# harp_behavior.net
KiCad netlist of a schematic drawn in EAGLE
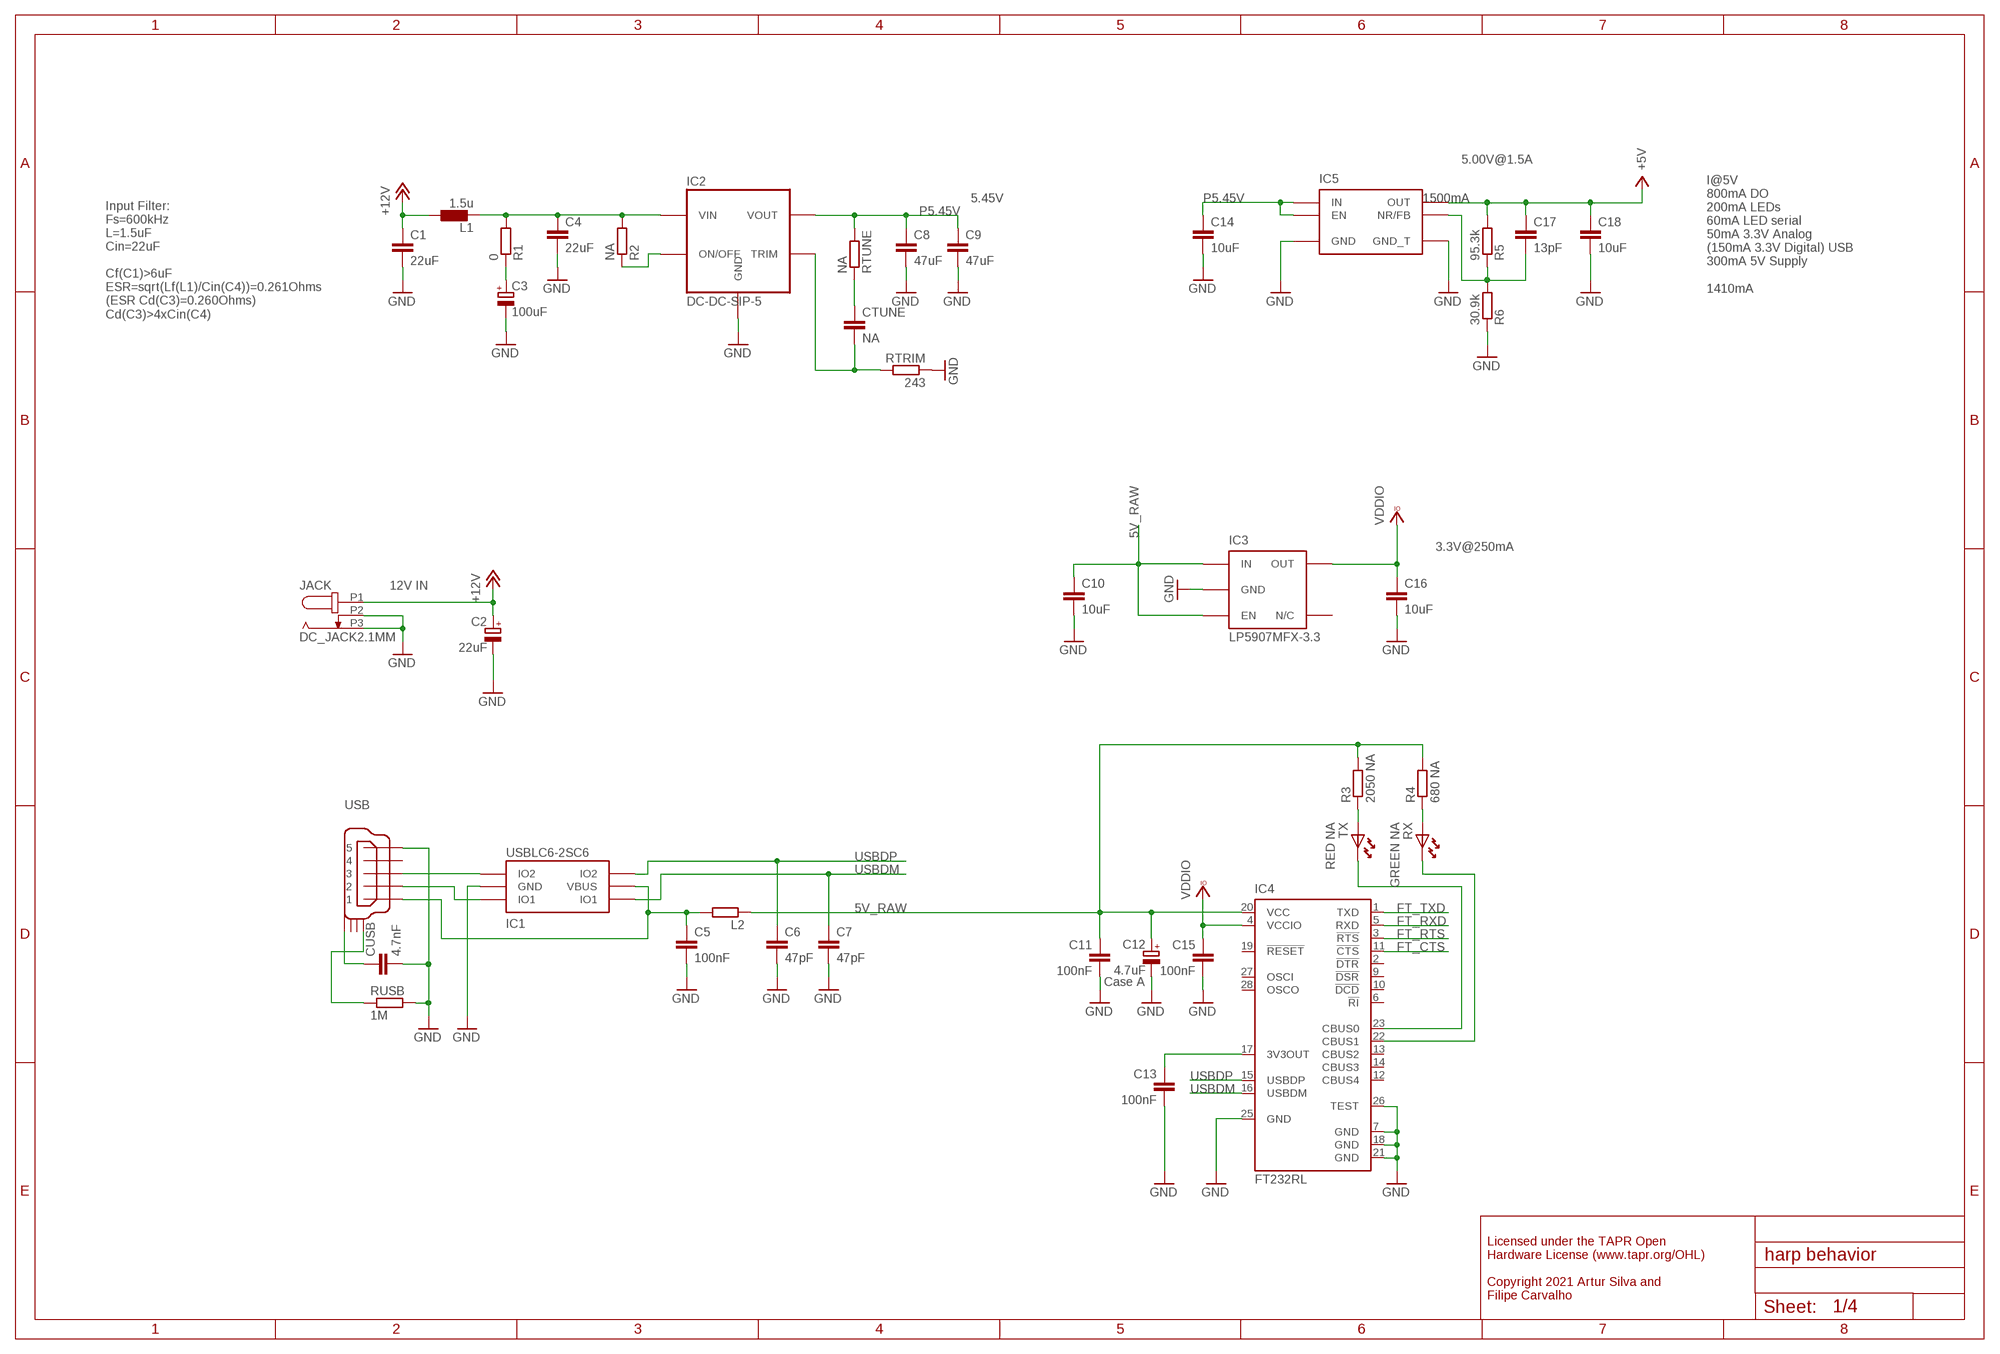
[diagram p0: schematic, sheet 1]
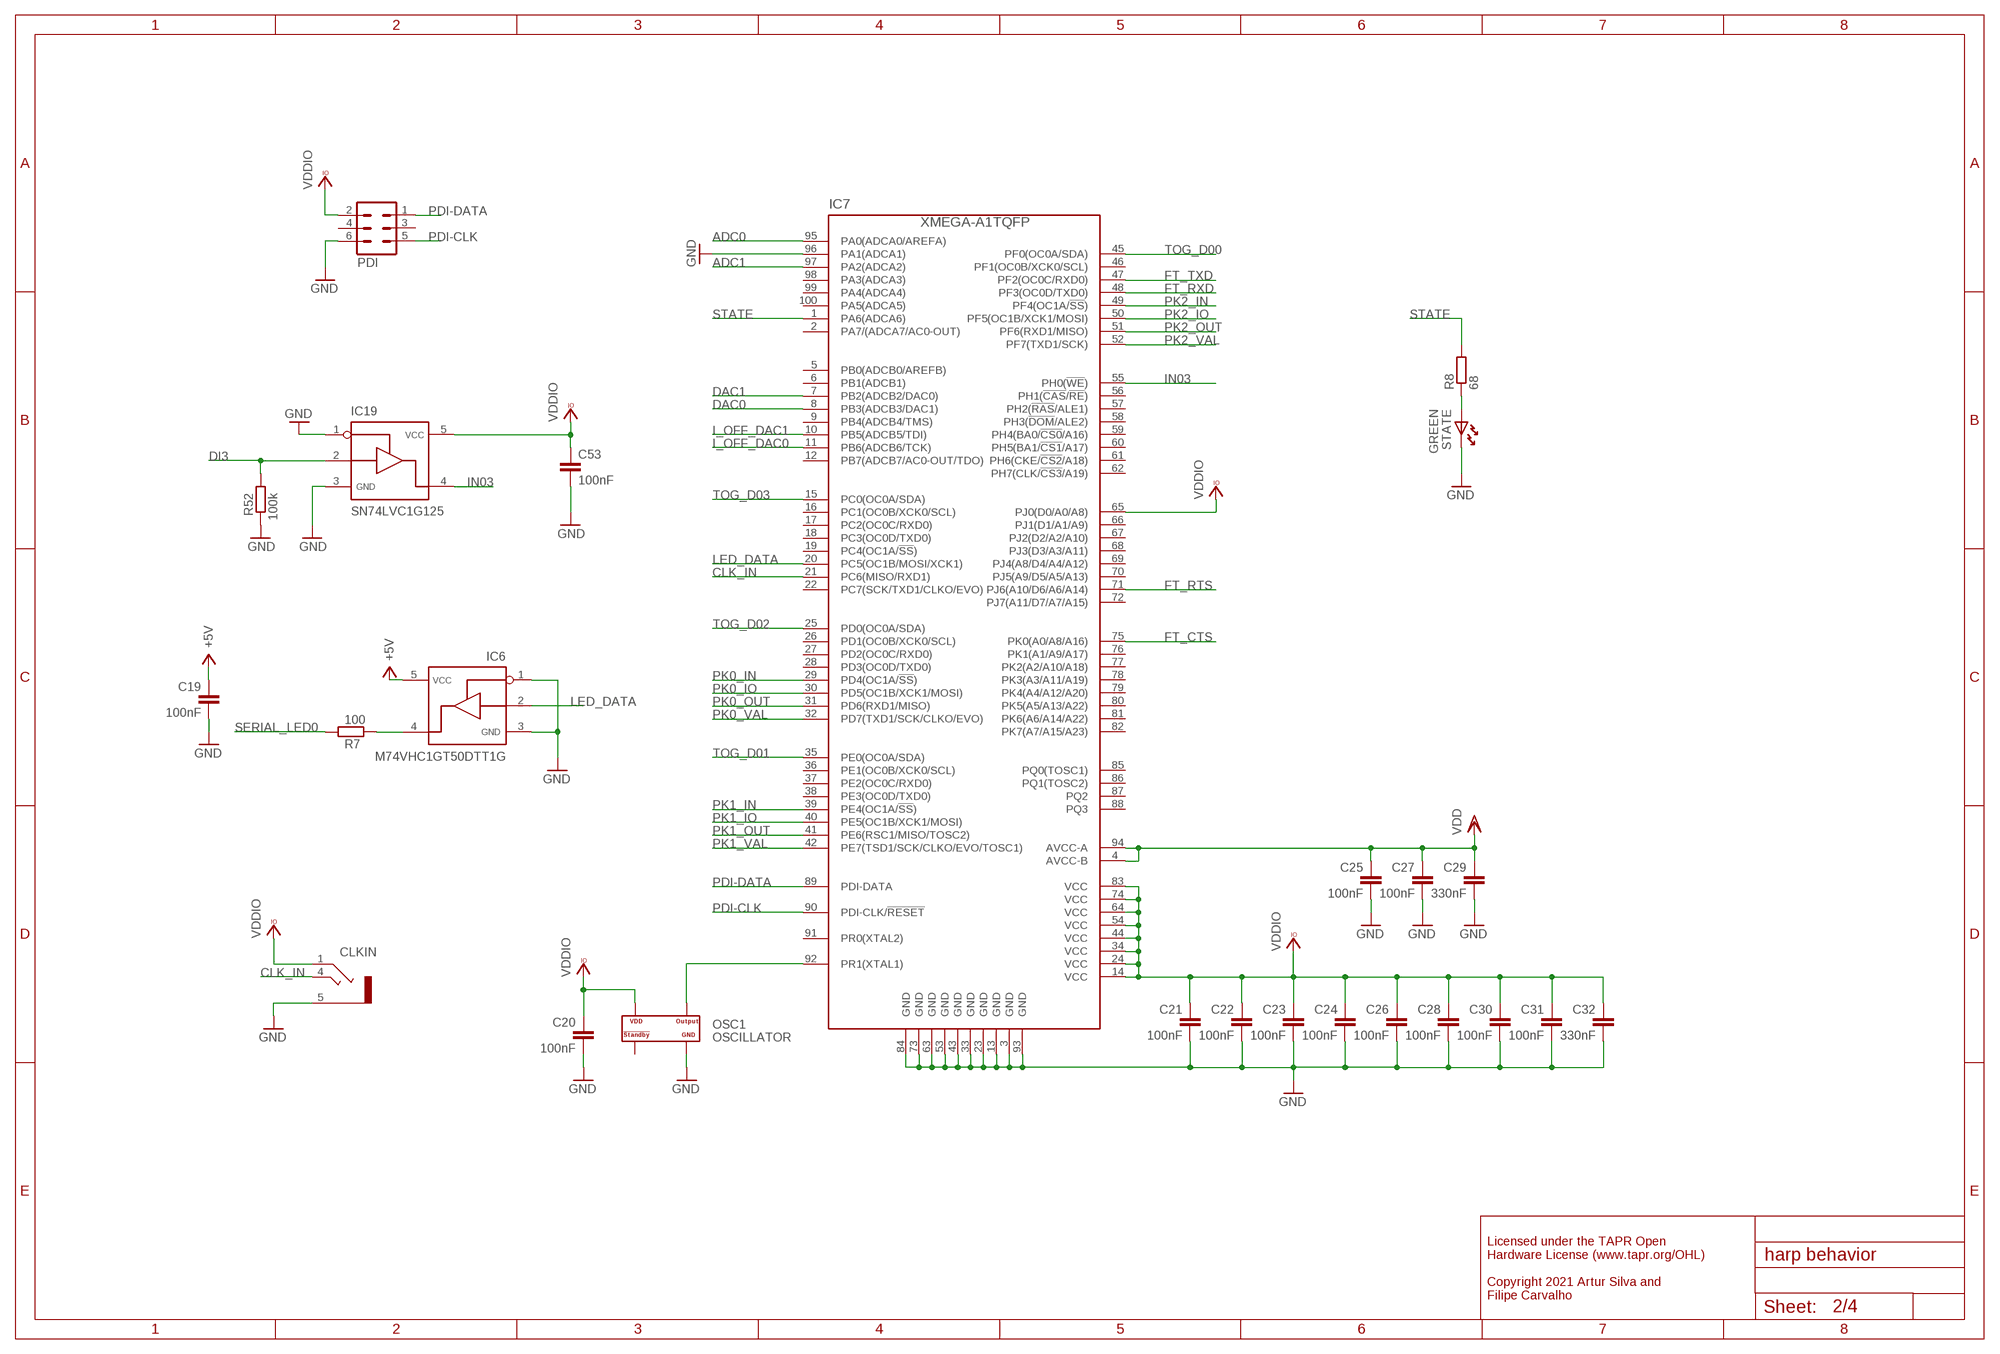
[diagram p1: schematic, sheet 2]
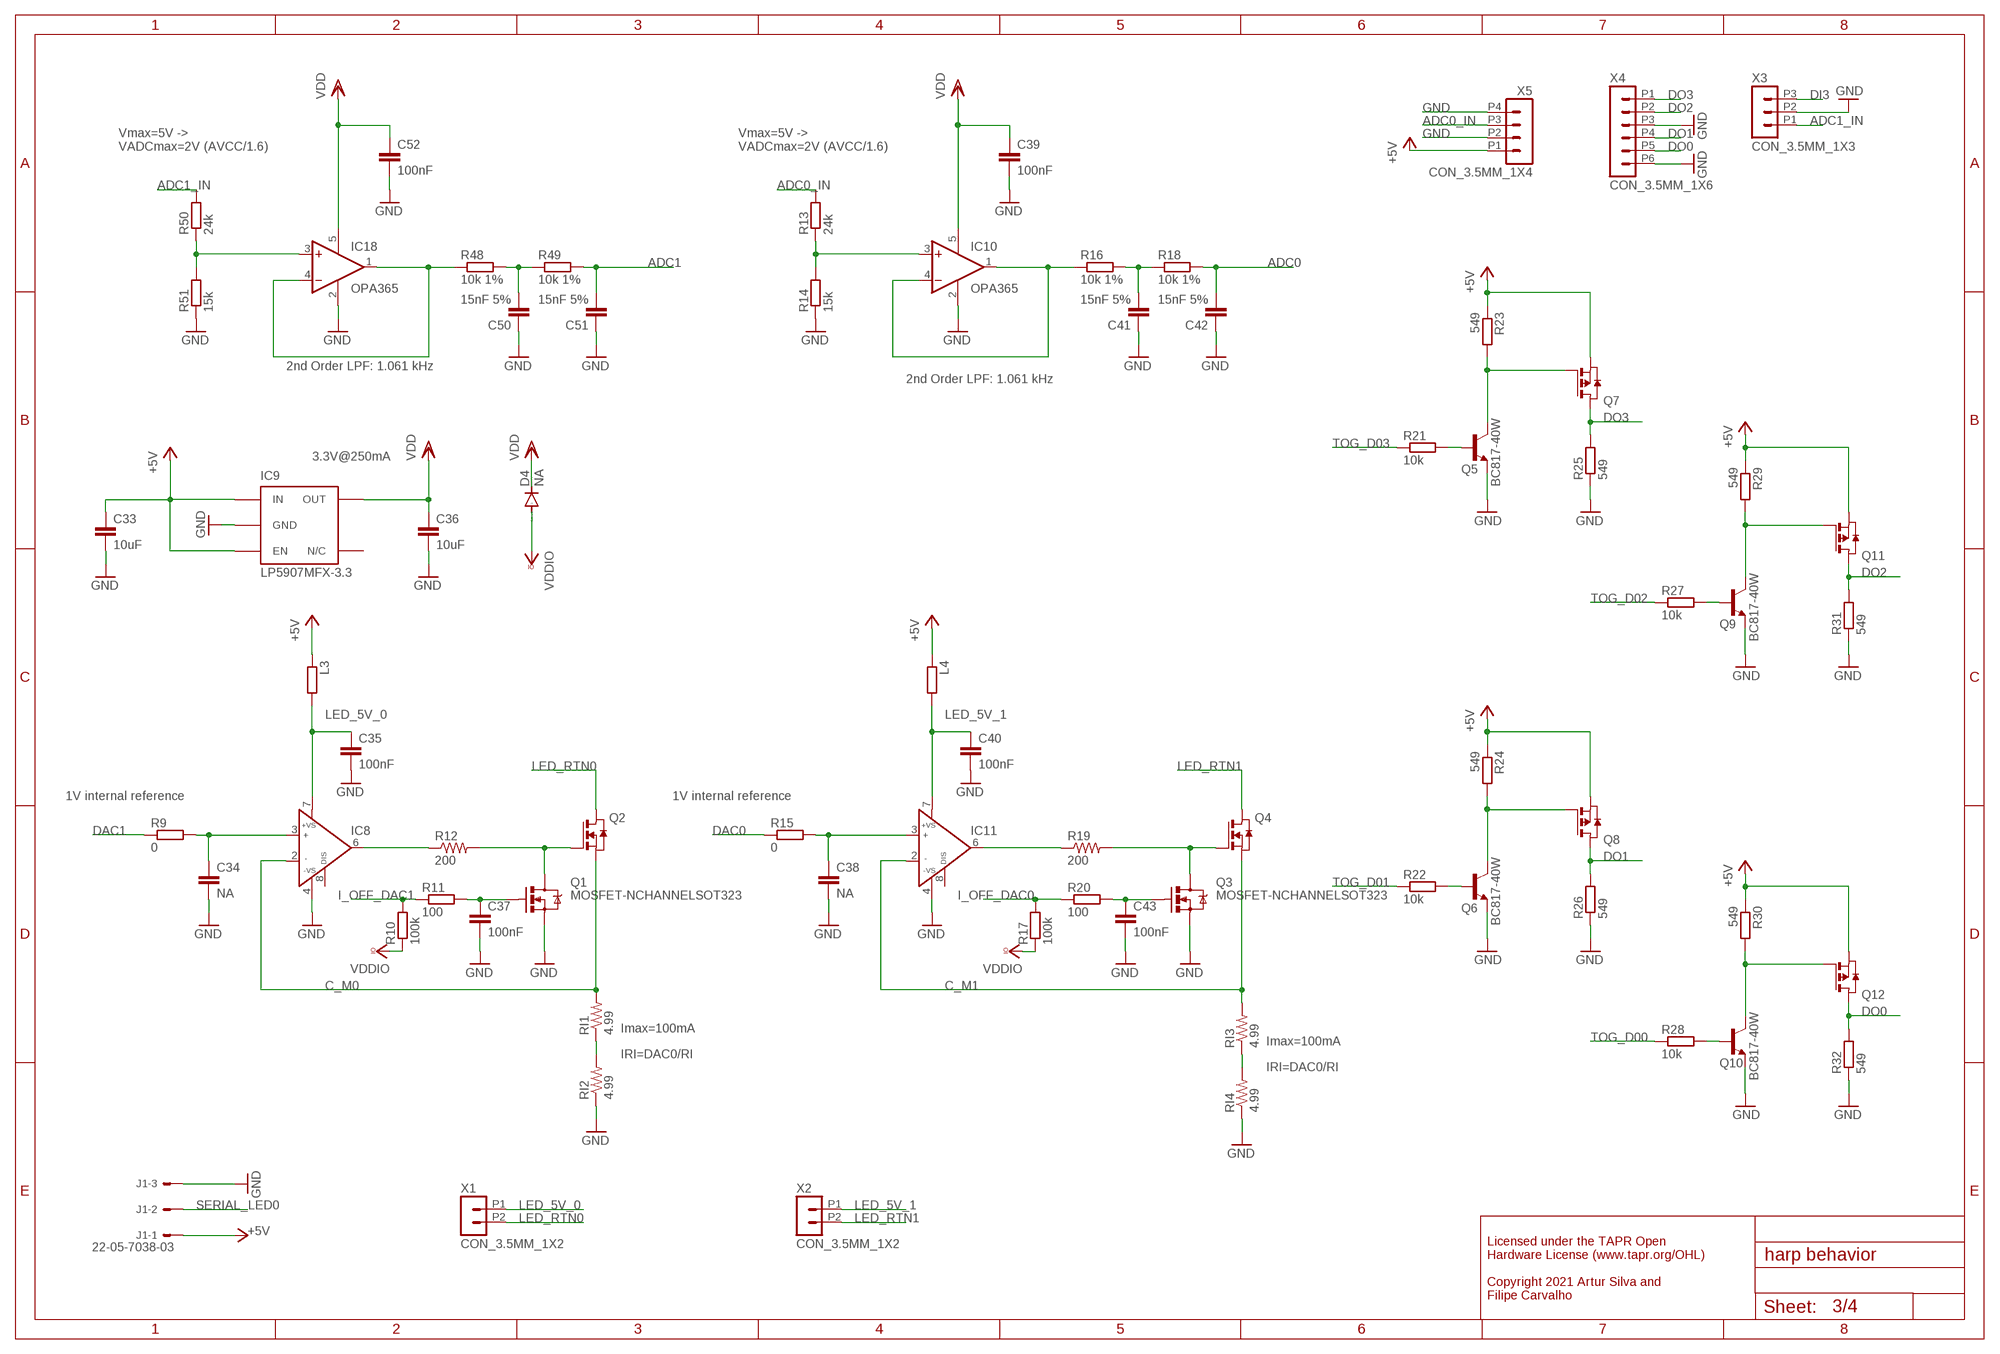
[diagram p2: schematic, sheet 3]
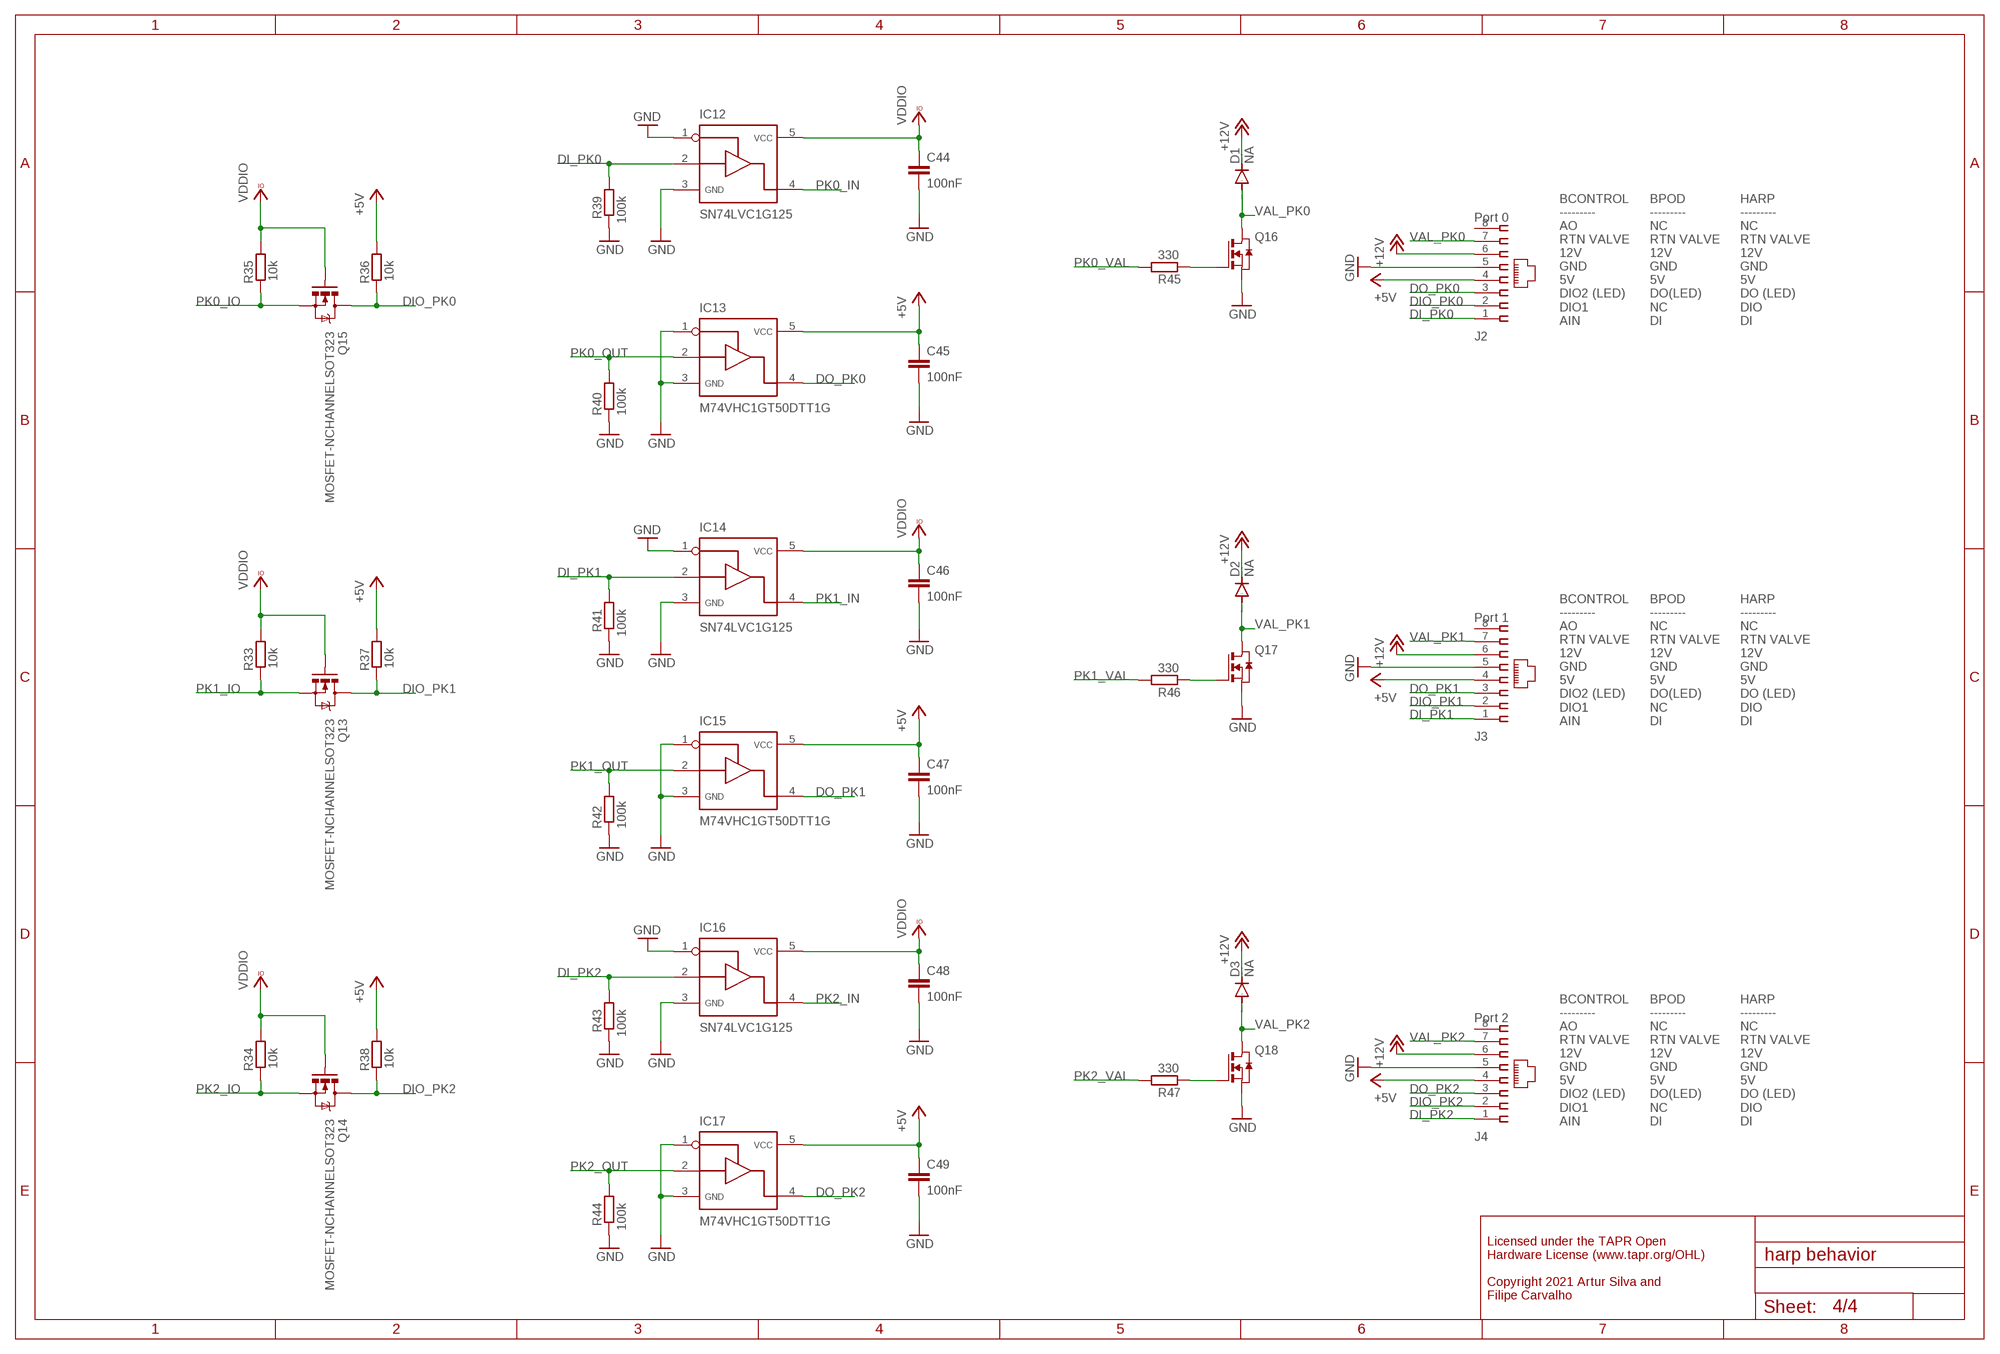
[diagram p3: schematic, sheet 4]

(export (version "E")
  (design (tool "Eeschema 10.0.6"))
  (components
    (comp (ref "C44")
      (value "100nF")
      (footprint "eagle-import:C0402")
      (libsource (lib "eagle-import") (part "C-EUC0402"))
    )
    (comp (ref "C45")
      (value "100nF")
      (footprint "eagle-import:C0402")
      (libsource (lib "eagle-import") (part "C-EUC0402"))
    )
    (comp (ref "C46")
      (value "100nF")
      (footprint "eagle-import:C0402")
      (libsource (lib "eagle-import") (part "C-EUC0402"))
    )
    (comp (ref "C47")
      (value "100nF")
      (footprint "eagle-import:C0402")
      (libsource (lib "eagle-import") (part "C-EUC0402"))
    )
    (comp (ref "C48")
      (value "100nF")
      (footprint "eagle-import:C0402")
      (libsource (lib "eagle-import") (part "C-EUC0402"))
    )
    (comp (ref "C49")
      (value "100nF")
      (footprint "eagle-import:C0402")
      (libsource (lib "eagle-import") (part "C-EUC0402"))
    )
    (comp (ref "D1")
      (value "NA")
      (footprint "eagle-import:SOD-323-DIODE")
      (libsource (lib "eagle-import") (part "DIODE"))
    )
    (comp (ref "D2")
      (value "NA")
      (footprint "eagle-import:SOD-323-DIODE")
      (libsource (lib "eagle-import") (part "DIODE"))
    )
    (comp (ref "D3")
      (value "NA")
      (footprint "eagle-import:SOD-323-DIODE")
      (libsource (lib "eagle-import") (part "DIODE"))
    )
    (comp (ref "IC12")
      (value "SN74LVC1G125")
      (footprint "eagle-import:SOT23-5")
      (libsource (lib "eagle-import") (part "SN74LVC1G125"))
    )
    (comp (ref "IC13")
      (value "M74VHC1GT50DTT1G")
      (footprint "eagle-import:SOT23-5")
      (libsource (lib "eagle-import") (part "SN74LVC1G125"))
    )
    (comp (ref "IC14")
      (value "SN74LVC1G125")
      (footprint "eagle-import:SOT23-5")
      (libsource (lib "eagle-import") (part "SN74LVC1G125"))
    )
    (comp (ref "IC15")
      (value "M74VHC1GT50DTT1G")
      (footprint "eagle-import:SOT23-5")
      (libsource (lib "eagle-import") (part "SN74LVC1G125"))
    )
    (comp (ref "IC16")
      (value "SN74LVC1G125")
      (footprint "eagle-import:SOT23-5")
      (libsource (lib "eagle-import") (part "SN74LVC1G125"))
    )
    (comp (ref "IC17")
      (value "M74VHC1GT50DTT1G")
      (footprint "eagle-import:SOT23-5")
      (libsource (lib "eagle-import") (part "SN74LVC1G125"))
    )
    (comp (ref "J2")
      (value "Port 0")
      (footprint "eagle-import:520426-4")
      (libsource (lib "eagle-import") (part "520426-4"))
    )
    (comp (ref "J3")
      (value "Port 1")
      (footprint "eagle-import:520426-4")
      (libsource (lib "eagle-import") (part "520426-4"))
    )
    (comp (ref "J4")
      (value "Port 2")
      (footprint "eagle-import:520426-4")
      (libsource (lib "eagle-import") (part "520426-4"))
    )
    (comp (ref "Q13")
      (value "MOSFET-NCHANNELSOT323")
      (footprint "eagle-import:SOT323")
      (libsource (lib "eagle-import") (part "MOSFET-NCHANNELSOT323"))
    )
    (comp (ref "Q14")
      (value "MOSFET-NCHANNELSOT323")
      (footprint "eagle-import:SOT323")
      (libsource (lib "eagle-import") (part "MOSFET-NCHANNELSOT323"))
    )
    (comp (ref "Q15")
      (value "MOSFET-NCHANNELSOT323")
      (footprint "eagle-import:SOT323")
      (libsource (lib "eagle-import") (part "MOSFET-NCHANNELSOT323"))
    )
    (comp (ref "Q16")
      (value "NMOSSOT223")
      (footprint "eagle-import:SOT223")
      (libsource (lib "eagle-import") (part "NMOSSOT223"))
    )
    (comp (ref "Q17")
      (value "NMOSSOT223")
      (footprint "eagle-import:SOT223")
      (libsource (lib "eagle-import") (part "NMOSSOT223"))
    )
    (comp (ref "Q18")
      (value "NMOSSOT223")
      (footprint "eagle-import:SOT223")
      (libsource (lib "eagle-import") (part "NMOSSOT223"))
    )
    (comp (ref "R33")
      (value "10k")
      (footprint "eagle-import:R0402")
      (libsource (lib "eagle-import") (part "R-EU_R0402"))
    )
    (comp (ref "R34")
      (value "10k")
      (footprint "eagle-import:R0402")
      (libsource (lib "eagle-import") (part "R-EU_R0402"))
    )
    (comp (ref "R35")
      (value "10k")
      (footprint "eagle-import:R0402")
      (libsource (lib "eagle-import") (part "R-EU_R0402"))
    )
    (comp (ref "R36")
      (value "10k")
      (footprint "eagle-import:R0402")
      (libsource (lib "eagle-import") (part "R-EU_R0402"))
    )
    (comp (ref "R37")
      (value "10k")
      (footprint "eagle-import:R0402")
      (libsource (lib "eagle-import") (part "R-EU_R0402"))
    )
    (comp (ref "R38")
      (value "10k")
      (footprint "eagle-import:R0402")
      (libsource (lib "eagle-import") (part "R-EU_R0402"))
    )
    (comp (ref "R39")
      (value "100k")
      (footprint "eagle-import:R0402")
      (libsource (lib "eagle-import") (part "R-EU_R0402"))
    )
    (comp (ref "R40")
      (value "100k")
      (footprint "eagle-import:R0402")
      (libsource (lib "eagle-import") (part "R-EU_R0402"))
    )
    (comp (ref "R41")
      (value "100k")
      (footprint "eagle-import:R0402")
      (libsource (lib "eagle-import") (part "R-EU_R0402"))
    )
    (comp (ref "R42")
      (value "100k")
      (footprint "eagle-import:R0402")
      (libsource (lib "eagle-import") (part "R-EU_R0402"))
    )
    (comp (ref "R43")
      (value "100k")
      (footprint "eagle-import:R0402")
      (libsource (lib "eagle-import") (part "R-EU_R0402"))
    )
    (comp (ref "R44")
      (value "100k")
      (footprint "eagle-import:R0402")
      (libsource (lib "eagle-import") (part "R-EU_R0402"))
    )
    (comp (ref "R45")
      (value "330")
      (footprint "eagle-import:R0402")
      (libsource (lib "eagle-import") (part "R-EU_R0402"))
    )
    (comp (ref "R46")
      (value "330")
      (footprint "eagle-import:R0402")
      (libsource (lib "eagle-import") (part "R-EU_R0402"))
    )
    (comp (ref "R47")
      (value "330")
      (footprint "eagle-import:R0402")
      (libsource (lib "eagle-import") (part "R-EU_R0402"))
    )
    (comp (ref "C1")
      (value "22uF")
      (footprint "eagle-import:C1210")
      (libsource (lib "eagle-import") (part "C-EUC1210"))
    )
    (comp (ref "C2")
      (value "22uF")
      (footprint "eagle-import:CAP_100UF_HAND")
      (libsource (lib "eagle-import") (part "CAP_100UFHAND"))
    )
    (comp (ref "C3")
      (value "100uF")
      (footprint "eagle-import:PANASONIC_E")
      (libsource (lib "eagle-import") (part "CPOL-EUE"))
    )
    (comp (ref "C4")
      (value "22uF")
      (footprint "eagle-import:C1210")
      (libsource (lib "eagle-import") (part "C-EUC1210"))
    )
    (comp (ref "C5")
      (value "100nF")
      (footprint "eagle-import:C0402")
      (libsource (lib "eagle-import") (part "C-EUC0402"))
    )
    (comp (ref "C6")
      (value "47pF")
      (footprint "eagle-import:C0402")
      (libsource (lib "eagle-import") (part "C-EUC0402"))
    )
    (comp (ref "C7")
      (value "47pF")
      (footprint "eagle-import:C0402")
      (libsource (lib "eagle-import") (part "C-EUC0402"))
    )
    (comp (ref "C8")
      (value "47uF")
      (footprint "eagle-import:C1210")
      (libsource (lib "eagle-import") (part "C-EUC1210"))
    )
    (comp (ref "C9")
      (value "47uF")
      (footprint "eagle-import:C1210")
      (libsource (lib "eagle-import") (part "C-EUC1210"))
    )
    (comp (ref "C10")
      (value "10uF")
      (footprint "eagle-import:C0603")
      (libsource (lib "eagle-import") (part "C-EUC0603"))
    )
    (comp (ref "C11")
      (value "100nF")
      (footprint "eagle-import:C0402")
      (libsource (lib "eagle-import") (part "C-EUC0402"))
    )
    (comp (ref "C12")
      (value "4.7uF")
      (footprint "eagle-import:A_3216-18W")
      (libsource (lib "eagle-import") (part "CPOL-EUA/3216-18W"))
    )
    (comp (ref "C13")
      (value "100nF")
      (footprint "eagle-import:C0402")
      (libsource (lib "eagle-import") (part "C-EUC0402"))
    )
    (comp (ref "C14")
      (value "10uF")
      (footprint "eagle-import:C0603")
      (libsource (lib "eagle-import") (part "C-EUC0603"))
    )
    (comp (ref "C15")
      (value "100nF")
      (footprint "eagle-import:C0402")
      (libsource (lib "eagle-import") (part "C-EUC0402"))
    )
    (comp (ref "C16")
      (value "10uF")
      (footprint "eagle-import:C0603")
      (libsource (lib "eagle-import") (part "C-EUC0603"))
    )
    (comp (ref "C17")
      (value "13pF")
      (footprint "eagle-import:C0402")
      (libsource (lib "eagle-import") (part "C-EUC0402"))
    )
    (comp (ref "C18")
      (value "10uF")
      (footprint "eagle-import:C0603")
      (libsource (lib "eagle-import") (part "C-EUC0603"))
    )
    (comp (ref "CTUNE")
      (value "NA")
      (footprint "eagle-import:C0402")
      (libsource (lib "eagle-import") (part "C-EUC0402"))
    )
    (comp (ref "CUSB")
      (value "4.7nF")
      (footprint "eagle-import:C0402")
      (libsource (lib "eagle-import") (part "C-EUC0402"))
    )
    (comp (ref "IC1")
      (value "USBLC6-2SC6")
      (footprint "eagle-import:SOT23-6L")
      (libsource (lib "eagle-import") (part "USBLC6-2"))
    )
    (comp (ref "IC2")
      (value "DC-DC-SIP-5")
      (footprint "eagle-import:SIP-5")
      (libsource (lib "eagle-import") (part "DC-DC-SIP-5"))
    )
    (comp (ref "IC3")
      (value "LP5907MFX-3.3")
      (footprint "eagle-import:TSOT23-5")
      (libsource (lib "eagle-import") (part "TLV700XX"))
    )
    (comp (ref "IC4")
      (value "FT232RL")
      (footprint "eagle-import:SSOP28")
      (libsource (lib "eagle-import") (part "FT232RL"))
    )
    (comp (ref "IC5")
      (value "TPS78601SON")
      (footprint "eagle-import:SON-8")
      (libsource (lib "eagle-import") (part "TPS78601SON"))
    )
    (comp (ref "JACK")
      (value "DC_JACK2.1MM")
      (footprint "eagle-import:DC_POWER_INPUT_2.1MM")
      (libsource (lib "eagle-import") (part "DC_JACK2.1MM"))
    )
    (comp (ref "L1")
      (value "1.5u")
      (footprint "eagle-import:IND_LPS4012_V2")
      (libsource (lib "eagle-import") (part "INDLPS4012_L"))
    )
    (comp (ref "L2")
      (value "???")
      (footprint "eagle-import:R0805")
      (libsource (lib "eagle-import") (part "R-EU_R0805"))
    )
    (comp (ref "R1")
      (value "0")
      (footprint "eagle-import:R0402")
      (libsource (lib "eagle-import") (part "R-EU_R0402"))
    )
    (comp (ref "R2")
      (value "NA")
      (footprint "eagle-import:R0402")
      (libsource (lib "eagle-import") (part "R-EU_R0402"))
    )
    (comp (ref "R3")
      (value "2050 NA")
      (footprint "eagle-import:R0402")
      (libsource (lib "eagle-import") (part "R-EU_R0402"))
    )
    (comp (ref "R4")
      (value "680 NA")
      (footprint "eagle-import:R0402")
      (libsource (lib "eagle-import") (part "R-EU_R0402"))
    )
    (comp (ref "R5")
      (value "95.3k")
      (footprint "eagle-import:R0402")
      (libsource (lib "eagle-import") (part "R-EU_R0402"))
    )
    (comp (ref "R6")
      (value "30.9k")
      (footprint "eagle-import:R0402")
      (libsource (lib "eagle-import") (part "R-EU_R0402"))
    )
    (comp (ref "RTRIM")
      (value "243")
      (footprint "eagle-import:R0402")
      (libsource (lib "eagle-import") (part "R-EU_R0402"))
    )
    (comp (ref "RTUNE")
      (value "NA")
      (footprint "eagle-import:R0402")
      (libsource (lib "eagle-import") (part "R-EU_R0402"))
    )
    (comp (ref "RUSB")
      (value "1M")
      (footprint "eagle-import:R0402")
      (libsource (lib "eagle-import") (part "R-EU_R0402"))
    )
    (comp (ref "RX")
      (value "GREEN NA")
      (footprint "eagle-import:LED_HAND")
      (libsource (lib "eagle-import") (part "LEDHAND"))
    )
    (comp (ref "TX")
      (value "RED NA")
      (footprint "eagle-import:LED_HAND")
      (libsource (lib "eagle-import") (part "LEDHAND"))
    )
    (comp (ref "USB")
      (value "USB_MINI_B")
      (footprint "eagle-import:240-0002-1")
      (libsource (lib "eagle-import") (part "USB_MINI_B"))
    )
    (comp (ref "C33")
      (value "10uF")
      (footprint "eagle-import:C0603")
      (libsource (lib "eagle-import") (part "C-EUC0603"))
    )
    (comp (ref "C34")
      (value "NA")
      (footprint "eagle-import:C0402")
      (libsource (lib "eagle-import") (part "C-EUC0402"))
    )
    (comp (ref "C35")
      (value "100nF")
      (footprint "eagle-import:C0402")
      (libsource (lib "eagle-import") (part "C-EUC0402"))
    )
    (comp (ref "C36")
      (value "10uF")
      (footprint "eagle-import:C0603")
      (libsource (lib "eagle-import") (part "C-EUC0603"))
    )
    (comp (ref "C37")
      (value "100nF")
      (footprint "eagle-import:C0402")
      (libsource (lib "eagle-import") (part "C-EUC0402"))
    )
    (comp (ref "C38")
      (value "NA")
      (footprint "eagle-import:C0402")
      (libsource (lib "eagle-import") (part "C-EUC0402"))
    )
    (comp (ref "C39")
      (value "100nF")
      (footprint "eagle-import:C0402")
      (libsource (lib "eagle-import") (part "C-EUC0402"))
    )
    (comp (ref "C40")
      (value "100nF")
      (footprint "eagle-import:C0402")
      (libsource (lib "eagle-import") (part "C-EUC0402"))
    )
    (comp (ref "C41")
      (value "15nF 5%")
      (footprint "eagle-import:C0402")
      (libsource (lib "eagle-import") (part "C-EUC0402"))
    )
    (comp (ref "C42")
      (value "15nF 5%")
      (footprint "eagle-import:C0402")
      (libsource (lib "eagle-import") (part "C-EUC0402"))
    )
    (comp (ref "C43")
      (value "100nF")
      (footprint "eagle-import:C0402")
      (libsource (lib "eagle-import") (part "C-EUC0402"))
    )
    (comp (ref "C50")
      (value "15nF 5%")
      (footprint "eagle-import:C0402")
      (libsource (lib "eagle-import") (part "C-EUC0402"))
    )
    (comp (ref "C51")
      (value "15nF 5%")
      (footprint "eagle-import:C0402")
      (libsource (lib "eagle-import") (part "C-EUC0402"))
    )
    (comp (ref "C52")
      (value "100nF")
      (footprint "eagle-import:C0402")
      (libsource (lib "eagle-import") (part "C-EUC0402"))
    )
    (comp (ref "D4")
      (value "NA")
      (footprint "eagle-import:SOD-323-DIODE")
      (libsource (lib "eagle-import") (part "DIODE"))
    )
    (comp (ref "IC8")
      (value "AD8041R")
      (footprint "eagle-import:SO8")
      (fields (field (name "MF") "ALTERA CORPORATION") (field (name "MPN") "AD8041ARZ"))
      (libsource (lib "eagle-import") (part "AD8041R"))
    )
    (comp (ref "IC9")
      (value "LP5907MFX-3.3")
      (footprint "eagle-import:TSOT23-5")
      (libsource (lib "eagle-import") (part "TLV700XX"))
    )
    (comp (ref "IC10")
      (value "OPA365")
      (footprint "eagle-import:SOT23-5")
      (libsource (lib "eagle-import") (part "OPA365"))
    )
    (comp (ref "IC11")
      (value "AD8041R")
      (footprint "eagle-import:SO8")
      (fields (field (name "MF") "ALTERA CORPORATION") (field (name "MPN") "AD8041ARZ"))
      (libsource (lib "eagle-import") (part "AD8041R"))
    )
    (comp (ref "IC18")
      (value "OPA365")
      (footprint "eagle-import:SOT23-5")
      (libsource (lib "eagle-import") (part "OPA365"))
    )
    (comp (ref "J1")
      (value "22-05-7038-03")
      (footprint "eagle-import:7395-03")
      (libsource (lib "eagle-import") (part "22-?-0305-7038"))
    )
    (comp (ref "L3")
      (value "600@100M")
      (footprint "eagle-import:R0805")
      (libsource (lib "eagle-import") (part "R-EU_R0805"))
    )
    (comp (ref "L4")
      (value "600@100M")
      (footprint "eagle-import:R0805")
      (libsource (lib "eagle-import") (part "R-EU_R0805"))
    )
    (comp (ref "Q1")
      (value "MOSFET-NCHANNELSOT323")
      (footprint "eagle-import:SOT323")
      (libsource (lib "eagle-import") (part "MOSFET-NCHANNELSOT323"))
    )
    (comp (ref "Q2")
      (value "NMOSSOT223")
      (footprint "eagle-import:SOT223")
      (libsource (lib "eagle-import") (part "NMOSSOT223"))
    )
    (comp (ref "Q3")
      (value "MOSFET-NCHANNELSOT323")
      (footprint "eagle-import:SOT323")
      (libsource (lib "eagle-import") (part "MOSFET-NCHANNELSOT323"))
    )
    (comp (ref "Q4")
      (value "NMOSSOT223")
      (footprint "eagle-import:SOT223")
      (libsource (lib "eagle-import") (part "NMOSSOT223"))
    )
    (comp (ref "Q5")
      (value "BC817-40W")
      (footprint "eagle-import:SOT323-BEC")
      (libsource (lib "eagle-import") (part "BC817"))
    )
    (comp (ref "Q6")
      (value "BC817-40W")
      (footprint "eagle-import:SOT323-BEC")
      (libsource (lib "eagle-import") (part "BC817"))
    )
    (comp (ref "Q7")
      (value "PMOSSOT223")
      (footprint "eagle-import:SOT223")
      (libsource (lib "eagle-import") (part "PMOSSOT223"))
    )
    (comp (ref "Q8")
      (value "PMOSSOT223")
      (footprint "eagle-import:SOT223")
      (libsource (lib "eagle-import") (part "PMOSSOT223"))
    )
    (comp (ref "Q9")
      (value "BC817-40W")
      (footprint "eagle-import:SOT323-BEC")
      (libsource (lib "eagle-import") (part "BC817"))
    )
    (comp (ref "Q10")
      (value "BC817-40W")
      (footprint "eagle-import:SOT323-BEC")
      (libsource (lib "eagle-import") (part "BC817"))
    )
    (comp (ref "Q11")
      (value "PMOSSOT223")
      (footprint "eagle-import:SOT223")
      (libsource (lib "eagle-import") (part "PMOSSOT223"))
    )
    (comp (ref "Q12")
      (value "PMOSSOT223")
      (footprint "eagle-import:SOT223")
      (libsource (lib "eagle-import") (part "PMOSSOT223"))
    )
    (comp (ref "R9")
      (value "0")
      (footprint "eagle-import:R0402")
      (libsource (lib "eagle-import") (part "R-EU_R0402"))
    )
    (comp (ref "R10")
      (value "100k")
      (footprint "eagle-import:R0402")
      (libsource (lib "eagle-import") (part "R-EU_R0402"))
    )
    (comp (ref "R11")
      (value "100")
      (footprint "eagle-import:R0402")
      (libsource (lib "eagle-import") (part "R-EU_R0402"))
    )
    (comp (ref "R12")
      (value "200")
      (footprint "eagle-import:R1210")
      (libsource (lib "eagle-import") (part "R-US_R1210"))
    )
    (comp (ref "R13")
      (value "24k")
      (footprint "eagle-import:R0402")
      (libsource (lib "eagle-import") (part "R-EU_R0402"))
    )
    (comp (ref "R14")
      (value "15k")
      (footprint "eagle-import:R0402")
      (libsource (lib "eagle-import") (part "R-EU_R0402"))
    )
    (comp (ref "R15")
      (value "0")
      (footprint "eagle-import:R0402")
      (libsource (lib "eagle-import") (part "R-EU_R0402"))
    )
    (comp (ref "R16")
      (value "10k 1%")
      (footprint "eagle-import:R0402")
      (libsource (lib "eagle-import") (part "R-EU_R0402"))
    )
    (comp (ref "R17")
      (value "100k")
      (footprint "eagle-import:R0402")
      (libsource (lib "eagle-import") (part "R-EU_R0402"))
    )
    (comp (ref "R18")
      (value "10k 1%")
      (footprint "eagle-import:R0402")
      (libsource (lib "eagle-import") (part "R-EU_R0402"))
    )
    (comp (ref "R19")
      (value "200")
      (footprint "eagle-import:R1210")
      (libsource (lib "eagle-import") (part "R-US_R1210"))
    )
    (comp (ref "R20")
      (value "100")
      (footprint "eagle-import:R0402")
      (libsource (lib "eagle-import") (part "R-EU_R0402"))
    )
    (comp (ref "R21")
      (value "10k")
      (footprint "eagle-import:R0402")
      (libsource (lib "eagle-import") (part "R-EU_R0402"))
    )
    (comp (ref "R22")
      (value "10k")
      (footprint "eagle-import:R0402")
      (libsource (lib "eagle-import") (part "R-EU_R0402"))
    )
    (comp (ref "R23")
      (value "549")
      (footprint "eagle-import:R0805")
      (libsource (lib "eagle-import") (part "R-EU_R0805"))
    )
    (comp (ref "R24")
      (value "549")
      (footprint "eagle-import:R0805")
      (libsource (lib "eagle-import") (part "R-EU_R0805"))
    )
    (comp (ref "R25")
      (value "549")
      (footprint "eagle-import:R0805")
      (libsource (lib "eagle-import") (part "R-EU_R0805"))
    )
    (comp (ref "R26")
      (value "549")
      (footprint "eagle-import:R0805")
      (libsource (lib "eagle-import") (part "R-EU_R0805"))
    )
    (comp (ref "R27")
      (value "10k")
      (footprint "eagle-import:R0402")
      (libsource (lib "eagle-import") (part "R-EU_R0402"))
    )
    (comp (ref "R28")
      (value "10k")
      (footprint "eagle-import:R0402")
      (libsource (lib "eagle-import") (part "R-EU_R0402"))
    )
    (comp (ref "R29")
      (value "549")
      (footprint "eagle-import:R0805")
      (libsource (lib "eagle-import") (part "R-EU_R0805"))
    )
    (comp (ref "R30")
      (value "549")
      (footprint "eagle-import:R0805")
      (libsource (lib "eagle-import") (part "R-EU_R0805"))
    )
    (comp (ref "R31")
      (value "549")
      (footprint "eagle-import:R0805")
      (libsource (lib "eagle-import") (part "R-EU_R0805"))
    )
    (comp (ref "R32")
      (value "549")
      (footprint "eagle-import:R0805")
      (libsource (lib "eagle-import") (part "R-EU_R0805"))
    )
    (comp (ref "R48")
      (value "10k 1%")
      (footprint "eagle-import:R0402")
      (libsource (lib "eagle-import") (part "R-EU_R0402"))
    )
    (comp (ref "R49")
      (value "10k 1%")
      (footprint "eagle-import:R0402")
      (libsource (lib "eagle-import") (part "R-EU_R0402"))
    )
    (comp (ref "R50")
      (value "24k")
      (footprint "eagle-import:R0402")
      (libsource (lib "eagle-import") (part "R-EU_R0402"))
    )
    (comp (ref "R51")
      (value "15k")
      (footprint "eagle-import:R0402")
      (libsource (lib "eagle-import") (part "R-EU_R0402"))
    )
    (comp (ref "RI1")
      (value "4.99")
      (footprint "eagle-import:R2512")
      (libsource (lib "eagle-import") (part "R-US_R2512"))
    )
    (comp (ref "RI2")
      (value "4.99")
      (footprint "eagle-import:R2512")
      (libsource (lib "eagle-import") (part "R-US_R2512"))
    )
    (comp (ref "RI3")
      (value "4.99")
      (footprint "eagle-import:R2512")
      (libsource (lib "eagle-import") (part "R-US_R2512"))
    )
    (comp (ref "RI4")
      (value "4.99")
      (footprint "eagle-import:R2512")
      (libsource (lib "eagle-import") (part "R-US_R2512"))
    )
    (comp (ref "X1")
      (value "CON_3.5MM_1X2")
      (footprint "eagle-import:CON_3.5MM_1X2")
      (libsource (lib "eagle-import") (part "CON_3.5MM_1X2"))
    )
    (comp (ref "X2")
      (value "CON_3.5MM_1X2")
      (footprint "eagle-import:CON_3.5MM_1X2")
      (libsource (lib "eagle-import") (part "CON_3.5MM_1X2"))
    )
    (comp (ref "X3")
      (value "CON_3.5MM_1X3")
      (footprint "eagle-import:CON_3.5MM_1X3")
      (libsource (lib "eagle-import") (part "CON_3.5MM_1X3"))
    )
    (comp (ref "X4")
      (value "CON_3.5MM_1X6")
      (footprint "eagle-import:CON_3.5MM_1X6")
      (libsource (lib "eagle-import") (part "CON_3.5MM_1X6"))
    )
    (comp (ref "X5")
      (value "CON_3.5MM_1X4")
      (footprint "eagle-import:CON_3.5MM_1X4")
      (libsource (lib "eagle-import") (part "CON_3.5MM_1X4"))
    )
    (comp (ref "C19")
      (value "100nF")
      (footprint "eagle-import:C0402")
      (libsource (lib "eagle-import") (part "C-EUC0402"))
    )
    (comp (ref "C20")
      (value "100nF")
      (footprint "eagle-import:C0402")
      (libsource (lib "eagle-import") (part "C-EUC0402"))
    )
    (comp (ref "C21")
      (value "100nF")
      (footprint "eagle-import:C0402")
      (libsource (lib "eagle-import") (part "C-EUC0402"))
    )
    (comp (ref "C22")
      (value "100nF")
      (footprint "eagle-import:C0402")
      (libsource (lib "eagle-import") (part "C-EUC0402"))
    )
    (comp (ref "C23")
      (value "100nF")
      (footprint "eagle-import:C0402")
      (libsource (lib "eagle-import") (part "C-EUC0402"))
    )
    (comp (ref "C24")
      (value "100nF")
      (footprint "eagle-import:C0402")
      (libsource (lib "eagle-import") (part "C-EUC0402"))
    )
    (comp (ref "C25")
      (value "100nF")
      (footprint "eagle-import:C0402")
      (libsource (lib "eagle-import") (part "C-EUC0402"))
    )
    (comp (ref "C26")
      (value "100nF")
      (footprint "eagle-import:C0402")
      (libsource (lib "eagle-import") (part "C-EUC0402"))
    )
    (comp (ref "C27")
      (value "100nF")
      (footprint "eagle-import:C0402")
      (libsource (lib "eagle-import") (part "C-EUC0402"))
    )
    (comp (ref "C28")
      (value "100nF")
      (footprint "eagle-import:C0402")
      (libsource (lib "eagle-import") (part "C-EUC0402"))
    )
    (comp (ref "C29")
      (value "330nF")
      (footprint "eagle-import:C0402")
      (libsource (lib "eagle-import") (part "C-EUC0402"))
    )
    (comp (ref "C30")
      (value "100nF")
      (footprint "eagle-import:C0402")
      (libsource (lib "eagle-import") (part "C-EUC0402"))
    )
    (comp (ref "C31")
      (value "100nF")
      (footprint "eagle-import:C0402")
      (libsource (lib "eagle-import") (part "C-EUC0402"))
    )
    (comp (ref "C32")
      (value "330nF")
      (footprint "eagle-import:C0402")
      (libsource (lib "eagle-import") (part "C-EUC0402"))
    )
    (comp (ref "C53")
      (value "100nF")
      (footprint "eagle-import:C0402")
      (libsource (lib "eagle-import") (part "C-EUC0402"))
    )
    (comp (ref "CLKIN")
      (value "STEREO_JACK")
      (footprint "eagle-import:35RASMT2BHNTRX")
      (libsource (lib "eagle-import") (part "STEREO_JACK"))
    )
    (comp (ref "IC6")
      (value "M74VHC1GT50DTT1G")
      (footprint "eagle-import:SOT23-5")
      (libsource (lib "eagle-import") (part "SN74LVC1G125"))
    )
    (comp (ref "IC7")
      (value "XMEGA-A1TQFP")
      (footprint "eagle-import:TQFP100")
      (libsource (lib "eagle-import") (part "XMEGA-A1TQFP"))
    )
    (comp (ref "IC19")
      (value "SN74LVC1G125")
      (footprint "eagle-import:SOT23-5")
      (libsource (lib "eagle-import") (part "SN74LVC1G125"))
    )
    (comp (ref "OSC1")
      (value "OSCILLATOR")
      (footprint "eagle-import:OSCILLATOR_3.2X2.5")
      (libsource (lib "eagle-import") (part "OSCILLATOR"))
    )
    (comp (ref "PDI")
      (value "MA03-2")
      (footprint "eagle-import:MA03-2")
      (libsource (lib "eagle-import") (part "MA03-2"))
    )
    (comp (ref "R7")
      (value "100")
      (footprint "eagle-import:R0402")
      (libsource (lib "eagle-import") (part "R-EU_R0402"))
    )
    (comp (ref "R8")
      (value "68")
      (footprint "eagle-import:R0402")
      (libsource (lib "eagle-import") (part "R-EU_R0402"))
    )
    (comp (ref "R52")
      (value "100k")
      (footprint "eagle-import:R0402")
      (libsource (lib "eagle-import") (part "R-EU_R0402"))
    )
    (comp (ref "STATE")
      (value "GREEN")
      (footprint "eagle-import:LED_HAND")
      (libsource (lib "eagle-import") (part "LEDHAND"))
    )
  )
  (nets
    (net (code "1") (name "+5V") (class "Default")
      (node (ref "C17") (pin "1") (pinfunction "1_1") (pintype "passive"))
      (node (ref "C18") (pin "1") (pinfunction "1_1") (pintype "passive"))
      (node (ref "C19") (pin "1") (pinfunction "1_1") (pintype "passive"))
      (node (ref "C33") (pin "1") (pinfunction "1_1") (pintype "passive"))
      (node (ref "C45") (pin "1") (pinfunction "1_1") (pintype "passive"))
      (node (ref "C47") (pin "1") (pinfunction "1_1") (pintype "passive"))
      (node (ref "C49") (pin "1") (pinfunction "1_1") (pintype "passive"))
      (node (ref "IC13") (pin "5") (pinfunction "P$5_5") (pintype "bidirectional"))
      (node (ref "IC15") (pin "5") (pinfunction "P$5_5") (pintype "bidirectional"))
      (node (ref "IC17") (pin "5") (pinfunction "P$5_5") (pintype "bidirectional"))
      (node (ref "IC5") (pin "P3") (pinfunction "OUT_P3") (pintype "bidirectional"))
      (node (ref "IC5") (pin "P4") (pinfunction "OUT_P4") (pintype "bidirectional"))
      (node (ref "IC6") (pin "5") (pinfunction "P$5_5") (pintype "bidirectional"))
      (node (ref "IC9") (pin "1") (pinfunction "IN_1") (pintype "bidirectional"))
      (node (ref "IC9") (pin "3") (pinfunction "EN_3") (pintype "bidirectional"))
      (node (ref "J1") (pin "1") (pinfunction "S_1") (pintype "passive"))
      (node (ref "J2") (pin "4") (pinfunction "4_4") (pintype "passive"))
      (node (ref "J3") (pin "4") (pinfunction "4_4") (pintype "passive"))
      (node (ref "J4") (pin "4") (pinfunction "4_4") (pintype "passive"))
      (node (ref "L3") (pin "1") (pinfunction "1_1") (pintype "passive"))
      (node (ref "L4") (pin "1") (pinfunction "1_1") (pintype "passive"))
      (node (ref "Q11") (pin "3") (pinfunction "S_3") (pintype "passive"))
      (node (ref "Q12") (pin "3") (pinfunction "S_3") (pintype "passive"))
      (node (ref "Q7") (pin "3") (pinfunction "S_3") (pintype "passive"))
      (node (ref "Q8") (pin "3") (pinfunction "S_3") (pintype "passive"))
      (node (ref "R23") (pin "1") (pinfunction "1_1") (pintype "passive"))
      (node (ref "R24") (pin "1") (pinfunction "1_1") (pintype "passive"))
      (node (ref "R29") (pin "1") (pinfunction "1_1") (pintype "passive"))
      (node (ref "R30") (pin "1") (pinfunction "1_1") (pintype "passive"))
      (node (ref "R36") (pin "1") (pinfunction "1_1") (pintype "passive"))
      (node (ref "R37") (pin "1") (pinfunction "1_1") (pintype "passive"))
      (node (ref "R38") (pin "1") (pinfunction "1_1") (pintype "passive"))
      (node (ref "R5") (pin "2") (pinfunction "2_2") (pintype "passive"))
      (node (ref "X5") (pin "P1") (pinfunction "1_P1") (pintype "passive"))
    )
    (net (code "2") (name "+12V") (class "Default")
      (node (ref "C1") (pin "1") (pinfunction "1_1") (pintype "passive"))
      (node (ref "C2") (pin "+") (pinfunction "+_+") (pintype "passive"))
      (node (ref "D1") (pin "C") (pinfunction "C_C") (pintype "passive"))
      (node (ref "D2") (pin "C") (pinfunction "C_C") (pintype "passive"))
      (node (ref "D3") (pin "C") (pinfunction "C_C") (pintype "passive"))
      (node (ref "J2") (pin "6") (pinfunction "6_6") (pintype "passive"))
      (node (ref "J3") (pin "6") (pinfunction "6_6") (pintype "passive"))
      (node (ref "J4") (pin "6") (pinfunction "6_6") (pintype "passive"))
      (node (ref "JACK") (pin "P1") (pinfunction "1_P1") (pintype "passive"))
      (node (ref "L1") (pin "1") (pinfunction "1_1") (pintype "passive"))
    )
    (net (code "3") (name "5V_RAW") (class "Default")
      (node (ref "C10") (pin "1") (pinfunction "1_1") (pintype "passive"))
      (node (ref "C11") (pin "1") (pinfunction "1_1") (pintype "passive"))
      (node (ref "C12") (pin "+") (pinfunction "+_+") (pintype "passive"))
      (node (ref "IC3") (pin "1") (pinfunction "IN_1") (pintype "bidirectional"))
      (node (ref "IC3") (pin "3") (pinfunction "EN_3") (pintype "bidirectional"))
      (node (ref "IC4") (pin "20") (pinfunction "VCC_20") (pintype "power_in"))
      (node (ref "L2") (pin "1") (pinfunction "1_1") (pintype "passive"))
      (node (ref "R3") (pin "2") (pinfunction "2_2") (pintype "passive"))
      (node (ref "R4") (pin "2") (pinfunction "2_2") (pintype "passive"))
    )
    (net (code "4") (name "ADC0") (class "Default")
      (node (ref "C42") (pin "2") (pinfunction "2_2") (pintype "passive"))
      (node (ref "IC7") (pin "95") (pinfunction "PA0(ADCA0/AREFA)_95") (pintype "bidirectional"))
      (node (ref "R18") (pin "2") (pinfunction "2_2") (pintype "passive"))
    )
    (net (code "5") (name "ADC0_IN") (class "Default")
      (node (ref "R13") (pin "2") (pinfunction "2_2") (pintype "passive"))
      (node (ref "X5") (pin "P3") (pinfunction "3_P3") (pintype "passive"))
    )
    (net (code "6") (name "ADC1") (class "Default")
      (node (ref "C51") (pin "2") (pinfunction "2_2") (pintype "passive"))
      (node (ref "IC7") (pin "97") (pinfunction "PA2(ADCA2)_97") (pintype "bidirectional"))
      (node (ref "R49") (pin "2") (pinfunction "2_2") (pintype "passive"))
    )
    (net (code "7") (name "ADC1_IN") (class "Default")
      (node (ref "R50") (pin "2") (pinfunction "2_2") (pintype "passive"))
      (node (ref "X3") (pin "P1") (pinfunction "1_P1") (pintype "passive"))
    )
    (net (code "8") (name "CLK_IN") (class "Default")
      (node (ref "CLKIN") (pin "4") (pinfunction "4_4") (pintype "passive"))
      (node (ref "IC7") (pin "21") (pinfunction "PC6(MISO/RXD1)_21") (pintype "bidirectional"))
    )
    (net (code "9") (name "C_M0") (class "Default")
      (node (ref "IC8") (pin "2") (pinfunction "IN-_2") (pintype "input"))
      (node (ref "Q2") (pin "3") (pinfunction "S_3") (pintype "passive"))
      (node (ref "RI1") (pin "2") (pinfunction "2_2") (pintype "passive"))
    )
    (net (code "10") (name "C_M1") (class "Default")
      (node (ref "IC11") (pin "2") (pinfunction "IN-_2") (pintype "input"))
      (node (ref "Q4") (pin "3") (pinfunction "S_3") (pintype "passive"))
      (node (ref "RI3") (pin "2") (pinfunction "2_2") (pintype "passive"))
    )
    (net (code "11") (name "DAC0") (class "Default")
      (node (ref "IC7") (pin "8") (pinfunction "PB3(ADCB3/DAC1)_8") (pintype "bidirectional"))
      (node (ref "R15") (pin "1") (pinfunction "1_1") (pintype "passive"))
    )
    (net (code "12") (name "DAC1") (class "Default")
      (node (ref "IC7") (pin "7") (pinfunction "PB2(ADCB2/DAC0)_7") (pintype "bidirectional"))
      (node (ref "R9") (pin "1") (pinfunction "1_1") (pintype "passive"))
    )
    (net (code "13") (name "DI3") (class "Default")
      (node (ref "IC19") (pin "2") (pinfunction "P$2_2") (pintype "bidirectional"))
      (node (ref "R52") (pin "1") (pinfunction "1_1") (pintype "passive"))
      (node (ref "X3") (pin "P3") (pinfunction "3_P3") (pintype "passive"))
    )
    (net (code "14") (name "DIO_PK0") (class "Default")
      (node (ref "J2") (pin "2") (pinfunction "2_2") (pintype "passive"))
      (node (ref "Q15") (pin "3") (pinfunction "D_3") (pintype "passive"))
      (node (ref "R36") (pin "2") (pinfunction "2_2") (pintype "passive"))
    )
    (net (code "15") (name "DIO_PK1") (class "Default")
      (node (ref "J3") (pin "2") (pinfunction "2_2") (pintype "passive"))
      (node (ref "Q13") (pin "3") (pinfunction "D_3") (pintype "passive"))
      (node (ref "R37") (pin "2") (pinfunction "2_2") (pintype "passive"))
    )
    (net (code "16") (name "DIO_PK2") (class "Default")
      (node (ref "J4") (pin "2") (pinfunction "2_2") (pintype "passive"))
      (node (ref "Q14") (pin "3") (pinfunction "D_3") (pintype "passive"))
      (node (ref "R38") (pin "2") (pinfunction "2_2") (pintype "passive"))
    )
    (net (code "17") (name "DI_PK0") (class "Default")
      (node (ref "IC12") (pin "2") (pinfunction "P$2_2") (pintype "bidirectional"))
      (node (ref "J2") (pin "1") (pinfunction "1_1") (pintype "passive"))
      (node (ref "R39") (pin "1") (pinfunction "1_1") (pintype "passive"))
    )
    (net (code "18") (name "DI_PK1") (class "Default")
      (node (ref "IC14") (pin "2") (pinfunction "P$2_2") (pintype "bidirectional"))
      (node (ref "J3") (pin "1") (pinfunction "1_1") (pintype "passive"))
      (node (ref "R41") (pin "1") (pinfunction "1_1") (pintype "passive"))
    )
    (net (code "19") (name "DI_PK2") (class "Default")
      (node (ref "IC16") (pin "2") (pinfunction "P$2_2") (pintype "bidirectional"))
      (node (ref "J4") (pin "1") (pinfunction "1_1") (pintype "passive"))
      (node (ref "R43") (pin "1") (pinfunction "1_1") (pintype "passive"))
    )
    (net (code "20") (name "DO0") (class "Default")
      (node (ref "Q12") (pin "2") (pinfunction "D_2") (pintype "passive"))
      (node (ref "Q12") (pin "4") (pinfunction "D_4") (pintype "passive"))
      (node (ref "R32") (pin "2") (pinfunction "2_2") (pintype "passive"))
      (node (ref "X4") (pin "P5") (pinfunction "5_P5") (pintype "passive"))
    )
    (net (code "21") (name "DO1") (class "Default")
      (node (ref "Q8") (pin "2") (pinfunction "D_2") (pintype "passive"))
      (node (ref "Q8") (pin "4") (pinfunction "D_4") (pintype "passive"))
      (node (ref "R26") (pin "2") (pinfunction "2_2") (pintype "passive"))
      (node (ref "X4") (pin "P4") (pinfunction "4_P4") (pintype "passive"))
    )
    (net (code "22") (name "DO2") (class "Default")
      (node (ref "Q11") (pin "2") (pinfunction "D_2") (pintype "passive"))
      (node (ref "Q11") (pin "4") (pinfunction "D_4") (pintype "passive"))
      (node (ref "R31") (pin "2") (pinfunction "2_2") (pintype "passive"))
      (node (ref "X4") (pin "P2") (pinfunction "2_P2") (pintype "passive"))
    )
    (net (code "23") (name "DO3") (class "Default")
      (node (ref "Q7") (pin "2") (pinfunction "D_2") (pintype "passive"))
      (node (ref "Q7") (pin "4") (pinfunction "D_4") (pintype "passive"))
      (node (ref "R25") (pin "2") (pinfunction "2_2") (pintype "passive"))
      (node (ref "X4") (pin "P1") (pinfunction "1_P1") (pintype "passive"))
    )
    (net (code "24") (name "DO_PK0") (class "Default")
      (node (ref "IC13") (pin "4") (pinfunction "P$4_4") (pintype "bidirectional"))
      (node (ref "J2") (pin "3") (pinfunction "3_3") (pintype "passive"))
    )
    (net (code "25") (name "DO_PK1") (class "Default")
      (node (ref "IC15") (pin "4") (pinfunction "P$4_4") (pintype "bidirectional"))
      (node (ref "J3") (pin "3") (pinfunction "3_3") (pintype "passive"))
    )
    (net (code "26") (name "DO_PK2") (class "Default")
      (node (ref "IC17") (pin "4") (pinfunction "P$4_4") (pintype "bidirectional"))
      (node (ref "J4") (pin "3") (pinfunction "3_3") (pintype "passive"))
    )
    (net (code "27") (name "FT_CTS") (class "Default")
      (node (ref "IC4") (pin "11") (pinfunction "~{CTS}_11") (pintype "input"))
      (node (ref "IC7") (pin "75") (pinfunction "PK0(A0/A8/A16)_75") (pintype "bidirectional"))
    )
    (net (code "28") (name "FT_RTS") (class "Default")
      (node (ref "IC4") (pin "3") (pinfunction "~{RTS}_3") (pintype "output"))
      (node (ref "IC7") (pin "71") (pinfunction "PJ6(A10/D6/A6/A14)_71") (pintype "bidirectional"))
    )
    (net (code "29") (name "FT_RXD") (class "Default")
      (node (ref "IC4") (pin "5") (pinfunction "RXD_5") (pintype "input"))
      (node (ref "IC7") (pin "48") (pinfunction "PF3(OC0D/TXD0)_48") (pintype "bidirectional"))
    )
    (net (code "30") (name "FT_TXD") (class "Default")
      (node (ref "IC4") (pin "1") (pinfunction "TXD_1") (pintype "output"))
      (node (ref "IC7") (pin "47") (pinfunction "PF2(OC0C/RXD0)_47") (pintype "bidirectional"))
    )
    (net (code "31") (name "GND") (class "Default")
      (node (ref "C1") (pin "2") (pinfunction "2_2") (pintype "passive"))
      (node (ref "C10") (pin "2") (pinfunction "2_2") (pintype "passive"))
      (node (ref "C11") (pin "2") (pinfunction "2_2") (pintype "passive"))
      (node (ref "C12") (pin "-") (pinfunction "-_-") (pintype "passive"))
      (node (ref "C13") (pin "2") (pinfunction "2_2") (pintype "passive"))
      (node (ref "C14") (pin "2") (pinfunction "2_2") (pintype "passive"))
      (node (ref "C15") (pin "2") (pinfunction "2_2") (pintype "passive"))
      (node (ref "C16") (pin "2") (pinfunction "2_2") (pintype "passive"))
      (node (ref "C18") (pin "2") (pinfunction "2_2") (pintype "passive"))
      (node (ref "C19") (pin "2") (pinfunction "2_2") (pintype "passive"))
      (node (ref "C2") (pin "-") (pinfunction "-_-") (pintype "passive"))
      (node (ref "C20") (pin "2") (pinfunction "2_2") (pintype "passive"))
      (node (ref "C21") (pin "2") (pinfunction "2_2") (pintype "passive"))
      (node (ref "C22") (pin "2") (pinfunction "2_2") (pintype "passive"))
      (node (ref "C23") (pin "2") (pinfunction "2_2") (pintype "passive"))
      (node (ref "C24") (pin "2") (pinfunction "2_2") (pintype "passive"))
      (node (ref "C25") (pin "2") (pinfunction "2_2") (pintype "passive"))
      (node (ref "C26") (pin "2") (pinfunction "2_2") (pintype "passive"))
      (node (ref "C27") (pin "2") (pinfunction "2_2") (pintype "passive"))
      (node (ref "C28") (pin "2") (pinfunction "2_2") (pintype "passive"))
      (node (ref "C29") (pin "2") (pinfunction "2_2") (pintype "passive"))
      (node (ref "C3") (pin "-") (pinfunction "-_-") (pintype "passive"))
      (node (ref "C30") (pin "2") (pinfunction "2_2") (pintype "passive"))
      (node (ref "C31") (pin "2") (pinfunction "2_2") (pintype "passive"))
      (node (ref "C32") (pin "2") (pinfunction "2_2") (pintype "passive"))
      (node (ref "C33") (pin "2") (pinfunction "2_2") (pintype "passive"))
      (node (ref "C34") (pin "2") (pinfunction "2_2") (pintype "passive"))
      (node (ref "C35") (pin "2") (pinfunction "2_2") (pintype "passive"))
      (node (ref "C36") (pin "2") (pinfunction "2_2") (pintype "passive"))
      (node (ref "C37") (pin "2") (pinfunction "2_2") (pintype "passive"))
      (node (ref "C38") (pin "2") (pinfunction "2_2") (pintype "passive"))
      (node (ref "C39") (pin "2") (pinfunction "2_2") (pintype "passive"))
      (node (ref "C4") (pin "2") (pinfunction "2_2") (pintype "passive"))
      (node (ref "C40") (pin "2") (pinfunction "2_2") (pintype "passive"))
      (node (ref "C41") (pin "1") (pinfunction "1_1") (pintype "passive"))
      (node (ref "C42") (pin "1") (pinfunction "1_1") (pintype "passive"))
      (node (ref "C43") (pin "2") (pinfunction "2_2") (pintype "passive"))
      (node (ref "C44") (pin "2") (pinfunction "2_2") (pintype "passive"))
      (node (ref "C45") (pin "2") (pinfunction "2_2") (pintype "passive"))
      (node (ref "C46") (pin "2") (pinfunction "2_2") (pintype "passive"))
      (node (ref "C47") (pin "2") (pinfunction "2_2") (pintype "passive"))
      (node (ref "C48") (pin "2") (pinfunction "2_2") (pintype "passive"))
      (node (ref "C49") (pin "2") (pinfunction "2_2") (pintype "passive"))
      (node (ref "C5") (pin "2") (pinfunction "2_2") (pintype "passive"))
      (node (ref "C50") (pin "1") (pinfunction "1_1") (pintype "passive"))
      (node (ref "C51") (pin "1") (pinfunction "1_1") (pintype "passive"))
      (node (ref "C52") (pin "2") (pinfunction "2_2") (pintype "passive"))
      (node (ref "C53") (pin "2") (pinfunction "2_2") (pintype "passive"))
      (node (ref "C6") (pin "2") (pinfunction "2_2") (pintype "passive"))
      (node (ref "C7") (pin "2") (pinfunction "2_2") (pintype "passive"))
      (node (ref "C8") (pin "2") (pinfunction "2_2") (pintype "passive"))
      (node (ref "C9") (pin "2") (pinfunction "2_2") (pintype "passive"))
      (node (ref "CLKIN") (pin "5") (pinfunction "5_5") (pintype "passive"))
      (node (ref "CUSB") (pin "2") (pinfunction "2_2") (pintype "passive"))
      (node (ref "IC1") (pin "P$2") (pinfunction "GND_P$2") (pintype "bidirectional"))
      (node (ref "IC10") (pin "2") (pinfunction "V-_2") (pintype "power_in"))
      (node (ref "IC11") (pin "4") (pinfunction "-VS_4") (pintype "input"))
      (node (ref "IC12") (pin "1") (pinfunction "P$1_1") (pintype "bidirectional"))
      (node (ref "IC12") (pin "3") (pinfunction "P$3_3") (pintype "bidirectional"))
      (node (ref "IC13") (pin "1") (pinfunction "P$1_1") (pintype "bidirectional"))
      (node (ref "IC13") (pin "3") (pinfunction "P$3_3") (pintype "bidirectional"))
      (node (ref "IC14") (pin "1") (pinfunction "P$1_1") (pintype "bidirectional"))
      (node (ref "IC14") (pin "3") (pinfunction "P$3_3") (pintype "bidirectional"))
      (node (ref "IC15") (pin "1") (pinfunction "P$1_1") (pintype "bidirectional"))
      (node (ref "IC15") (pin "3") (pinfunction "P$3_3") (pintype "bidirectional"))
      (node (ref "IC16") (pin "1") (pinfunction "P$1_1") (pintype "bidirectional"))
      (node (ref "IC16") (pin "3") (pinfunction "P$3_3") (pintype "bidirectional"))
      (node (ref "IC17") (pin "1") (pinfunction "P$1_1") (pintype "bidirectional"))
      (node (ref "IC17") (pin "3") (pinfunction "P$3_3") (pintype "bidirectional"))
      (node (ref "IC18") (pin "2") (pinfunction "V-_2") (pintype "power_in"))
      (node (ref "IC19") (pin "1") (pinfunction "P$1_1") (pintype "bidirectional"))
      (node (ref "IC19") (pin "3") (pinfunction "P$3_3") (pintype "bidirectional"))
      (node (ref "IC2") (pin "P3") (pinfunction "GND_P3") (pintype "passive"))
      (node (ref "IC3") (pin "2") (pinfunction "GND_2") (pintype "bidirectional"))
      (node (ref "IC4") (pin "18") (pinfunction "GND_18") (pintype "power_in"))
      (node (ref "IC4") (pin "21") (pinfunction "GND_21") (pintype "power_in"))
      (node (ref "IC4") (pin "25") (pinfunction "GND_25") (pintype "power_in"))
      (node (ref "IC4") (pin "26") (pinfunction "TEST_26") (pintype "input"))
      (node (ref "IC4") (pin "7") (pinfunction "GND_7") (pintype "power_in"))
      (node (ref "IC5") (pin "P6") (pinfunction "GND_P6") (pintype "bidirectional"))
      (node (ref "IC5") (pin "P9") (pinfunction "GND_T_P9") (pintype "bidirectional"))
      (node (ref "IC6") (pin "1") (pinfunction "P$1_1") (pintype "bidirectional"))
      (node (ref "IC6") (pin "3") (pinfunction "P$3_3") (pintype "bidirectional"))
      (node (ref "IC7") (pin "13") (pinfunction "GND_13") (pintype "power_in"))
      (node (ref "IC7") (pin "23") (pinfunction "GND_23") (pintype "power_in"))
      (node (ref "IC7") (pin "3") (pinfunction "GND_3") (pintype "power_in"))
      (node (ref "IC7") (pin "33") (pinfunction "GND_33") (pintype "power_in"))
      (node (ref "IC7") (pin "43") (pinfunction "GND_43") (pintype "power_in"))
      (node (ref "IC7") (pin "53") (pinfunction "GND_53") (pintype "power_in"))
      (node (ref "IC7") (pin "63") (pinfunction "GND_63") (pintype "power_in"))
      (node (ref "IC7") (pin "73") (pinfunction "GND_73") (pintype "power_in"))
      (node (ref "IC7") (pin "84") (pinfunction "GND_84") (pintype "power_in"))
      (node (ref "IC7") (pin "93") (pinfunction "GND_93") (pintype "power_in"))
      (node (ref "IC7") (pin "96") (pinfunction "PA1(ADCA1)_96") (pintype "bidirectional"))
      (node (ref "IC8") (pin "4") (pinfunction "-VS_4") (pintype "input"))
      (node (ref "IC9") (pin "2") (pinfunction "GND_2") (pintype "bidirectional"))
      (node (ref "J1") (pin "3") (pinfunction "S_3") (pintype "passive"))
      (node (ref "J2") (pin "5") (pinfunction "5_5") (pintype "passive"))
      (node (ref "J3") (pin "5") (pinfunction "5_5") (pintype "passive"))
      (node (ref "J4") (pin "5") (pinfunction "5_5") (pintype "passive"))
      (node (ref "JACK") (pin "P2") (pinfunction "2_P2") (pintype "passive"))
      (node (ref "JACK") (pin "P3") (pinfunction "3_P3") (pintype "passive"))
      (node (ref "OSC1") (pin "P$2") (pinfunction "GND_P$2") (pintype "passive"))
      (node (ref "PDI") (pin "6") (pinfunction "6_6") (pintype "passive"))
      (node (ref "Q1") (pin "2") (pinfunction "S_2") (pintype "passive"))
      (node (ref "Q10") (pin "E") (pinfunction "E_E") (pintype "passive"))
      (node (ref "Q16") (pin "3") (pinfunction "S_3") (pintype "passive"))
      (node (ref "Q17") (pin "3") (pinfunction "S_3") (pintype "passive"))
      (node (ref "Q18") (pin "3") (pinfunction "S_3") (pintype "passive"))
      (node (ref "Q3") (pin "2") (pinfunction "S_2") (pintype "passive"))
      (node (ref "Q5") (pin "E") (pinfunction "E_E") (pintype "passive"))
      (node (ref "Q6") (pin "E") (pinfunction "E_E") (pintype "passive"))
      (node (ref "Q9") (pin "E") (pinfunction "E_E") (pintype "passive"))
      (node (ref "R14") (pin "1") (pinfunction "1_1") (pintype "passive"))
      (node (ref "R25") (pin "1") (pinfunction "1_1") (pintype "passive"))
      (node (ref "R26") (pin "1") (pinfunction "1_1") (pintype "passive"))
      (node (ref "R31") (pin "1") (pinfunction "1_1") (pintype "passive"))
      (node (ref "R32") (pin "1") (pinfunction "1_1") (pintype "passive"))
      (node (ref "R39") (pin "2") (pinfunction "2_2") (pintype "passive"))
      (node (ref "R40") (pin "1") (pinfunction "1_1") (pintype "passive"))
      (node (ref "R41") (pin "2") (pinfunction "2_2") (pintype "passive"))
      (node (ref "R42") (pin "1") (pinfunction "1_1") (pintype "passive"))
      (node (ref "R43") (pin "2") (pinfunction "2_2") (pintype "passive"))
      (node (ref "R44") (pin "2") (pinfunction "2_2") (pintype "passive"))
      (node (ref "R51") (pin "1") (pinfunction "1_1") (pintype "passive"))
      (node (ref "R52") (pin "2") (pinfunction "2_2") (pintype "passive"))
      (node (ref "R6") (pin "1") (pinfunction "1_1") (pintype "passive"))
      (node (ref "RI2") (pin "1") (pinfunction "1_1") (pintype "passive"))
      (node (ref "RI4") (pin "1") (pinfunction "1_1") (pintype "passive"))
      (node (ref "RTRIM") (pin "1") (pinfunction "1_1") (pintype "passive"))
      (node (ref "RUSB") (pin "2") (pinfunction "2_2") (pintype "passive"))
      (node (ref "STATE") (pin "K") (pinfunction "K_K") (pintype "bidirectional"))
      (node (ref "USB") (pin "P$5") (pinfunction "5_P$5") (pintype "bidirectional"))
      (node (ref "X3") (pin "P2") (pinfunction "2_P2") (pintype "passive"))
      (node (ref "X4") (pin "P3") (pinfunction "3_P3") (pintype "passive"))
      (node (ref "X4") (pin "P6") (pinfunction "6_P6") (pintype "passive"))
      (node (ref "X5") (pin "P2") (pinfunction "2_P2") (pintype "passive"))
      (node (ref "X5") (pin "P4") (pinfunction "4_P4") (pintype "passive"))
    )
    (net (code "32") (name "IN03") (class "Default")
      (node (ref "IC19") (pin "4") (pinfunction "P$4_4") (pintype "bidirectional"))
      (node (ref "IC7") (pin "55") (pinfunction "PH0(~{WE})_55") (pintype "bidirectional"))
    )
    (net (code "33") (name "I_OFF_DAC0") (class "Default")
      (node (ref "IC7") (pin "11") (pinfunction "PB6(ADCB6/TCK)_11") (pintype "bidirectional"))
      (node (ref "R17") (pin "2") (pinfunction "2_2") (pintype "passive"))
      (node (ref "R20") (pin "1") (pinfunction "1_1") (pintype "passive"))
    )
    (net (code "34") (name "I_OFF_DAC1") (class "Default")
      (node (ref "IC7") (pin "10") (pinfunction "PB5(ADCB5/TDI)_10") (pintype "bidirectional"))
      (node (ref "R10") (pin "2") (pinfunction "2_2") (pintype "passive"))
      (node (ref "R11") (pin "1") (pinfunction "1_1") (pintype "passive"))
    )
    (net (code "35") (name "LED_5V_0") (class "Default")
      (node (ref "C35") (pin "1") (pinfunction "1_1") (pintype "passive"))
      (node (ref "IC8") (pin "7") (pinfunction "+VS_7") (pintype "input"))
      (node (ref "L3") (pin "2") (pinfunction "2_2") (pintype "passive"))
      (node (ref "X1") (pin "P1") (pinfunction "1_P1") (pintype "passive"))
    )
    (net (code "36") (name "LED_5V_1") (class "Default")
      (node (ref "C40") (pin "1") (pinfunction "1_1") (pintype "passive"))
      (node (ref "IC11") (pin "7") (pinfunction "+VS_7") (pintype "input"))
      (node (ref "L4") (pin "2") (pinfunction "2_2") (pintype "passive"))
      (node (ref "X2") (pin "P1") (pinfunction "1_P1") (pintype "passive"))
    )
    (net (code "37") (name "LED_DATA") (class "Default")
      (node (ref "IC6") (pin "2") (pinfunction "P$2_2") (pintype "bidirectional"))
      (node (ref "IC7") (pin "20") (pinfunction "PC5(OC1B/MOSI/XCK1)_20") (pintype "bidirectional"))
    )
    (net (code "38") (name "LED_RTN0") (class "Default")
      (node (ref "Q2") (pin "2") (pinfunction "D_2") (pintype "passive"))
      (node (ref "Q2") (pin "4") (pinfunction "D_4") (pintype "passive"))
      (node (ref "X1") (pin "P2") (pinfunction "2_P2") (pintype "passive"))
    )
    (net (code "39") (name "LED_RTN1") (class "Default")
      (node (ref "Q4") (pin "2") (pinfunction "D_2") (pintype "passive"))
      (node (ref "Q4") (pin "4") (pinfunction "D_4") (pintype "passive"))
      (node (ref "X2") (pin "P2") (pinfunction "2_P2") (pintype "passive"))
    )
    (net (code "40") (name "Net-(C3-Pad+)") (class "Default")
      (node (ref "C3") (pin "+") (pinfunction "+_+") (pintype "passive"))
      (node (ref "R1") (pin "1") (pinfunction "1_1") (pintype "passive"))
    )
    (net (code "41") (name "Net-(C41-Pad2)") (class "Default")
      (node (ref "C41") (pin "2") (pinfunction "2_2") (pintype "passive"))
      (node (ref "R16") (pin "2") (pinfunction "2_2") (pintype "passive"))
      (node (ref "R18") (pin "1") (pinfunction "1_1") (pintype "passive"))
    )
    (net (code "42") (name "Net-(C50-Pad2)") (class "Default")
      (node (ref "C50") (pin "2") (pinfunction "2_2") (pintype "passive"))
      (node (ref "R48") (pin "2") (pinfunction "2_2") (pintype "passive"))
      (node (ref "R49") (pin "1") (pinfunction "1_1") (pintype "passive"))
    )
    (net (code "43") (name "Net-(CTUNE-Pad1)") (class "Default")
      (node (ref "CTUNE") (pin "1") (pinfunction "1_1") (pintype "passive"))
      (node (ref "RTUNE") (pin "1") (pinfunction "1_1") (pintype "passive"))
    )
    (net (code "44") (name "Net-(IC1-VBUS)") (class "Default")
      (node (ref "C5") (pin "1") (pinfunction "1_1") (pintype "passive"))
      (node (ref "IC1") (pin "P$5") (pinfunction "VBUS_P$5") (pintype "bidirectional"))
      (node (ref "L2") (pin "2") (pinfunction "2_2") (pintype "passive"))
      (node (ref "USB") (pin "P$1") (pinfunction "1_P$1") (pintype "bidirectional"))
    )
    (net (code "45") (name "Net-(IC2-ON{slash}OFF)") (class "Default")
      (node (ref "IC2") (pin "P1") (pinfunction "ON/OFF_P1") (pintype "passive"))
      (node (ref "R2") (pin "1") (pinfunction "1_1") (pintype "passive"))
    )
    (net (code "46") (name "Net-(IC2-TRIM)") (class "Default")
      (node (ref "CTUNE") (pin "2") (pinfunction "2_2") (pintype "passive"))
      (node (ref "IC2") (pin "P5") (pinfunction "TRIM_P5") (pintype "passive"))
      (node (ref "RTRIM") (pin "2") (pinfunction "2_2") (pintype "passive"))
    )
    (net (code "47") (name "Net-(IC2-VIN)") (class "Default")
      (node (ref "C4") (pin "1") (pinfunction "1_1") (pintype "passive"))
      (node (ref "IC2") (pin "P2") (pinfunction "VIN_P2") (pintype "passive"))
      (node (ref "L1") (pin "2") (pinfunction "2_2") (pintype "passive"))
      (node (ref "R1") (pin "2") (pinfunction "2_2") (pintype "passive"))
      (node (ref "R2") (pin "2") (pinfunction "2_2") (pintype "passive"))
    )
    (net (code "48") (name "Net-(IC4-3V3OUT)") (class "Default")
      (node (ref "C13") (pin "1") (pinfunction "1_1") (pintype "passive"))
      (node (ref "IC4") (pin "17") (pinfunction "3V3OUT_17") (pintype "output"))
    )
    (net (code "49") (name "Net-(IC4-CBUS0)") (class "Default")
      (node (ref "IC4") (pin "23") (pinfunction "CBUS0_23") (pintype "bidirectional"))
      (node (ref "TX") (pin "K") (pinfunction "K_K") (pintype "bidirectional"))
    )
    (net (code "50") (name "Net-(IC4-CBUS1)") (class "Default")
      (node (ref "IC4") (pin "22") (pinfunction "CBUS1_22") (pintype "bidirectional"))
      (node (ref "RX") (pin "K") (pinfunction "K_K") (pintype "bidirectional"))
    )
    (net (code "51") (name "Net-(IC5-NR{slash}FB)") (class "Default")
      (node (ref "C17") (pin "2") (pinfunction "2_2") (pintype "passive"))
      (node (ref "IC5") (pin "P5") (pinfunction "NR/FB_P5") (pintype "bidirectional"))
      (node (ref "R5") (pin "1") (pinfunction "1_1") (pintype "passive"))
      (node (ref "R6") (pin "2") (pinfunction "2_2") (pintype "passive"))
    )
    (net (code "52") (name "Net-(IC6-P$4)") (class "Default")
      (node (ref "IC6") (pin "4") (pinfunction "P$4_4") (pintype "bidirectional"))
      (node (ref "R7") (pin "2") (pinfunction "2_2") (pintype "passive"))
    )
    (net (code "53") (name "Net-(IC7-PR1(XTAL1))") (class "Default")
      (node (ref "IC7") (pin "92") (pinfunction "PR1(XTAL1)_92") (pintype "bidirectional"))
      (node (ref "OSC1") (pin "P$3") (pinfunction "OUTPUT_P$3") (pintype "passive"))
    )
    (net (code "54") (name "Net-(IC8-IN+)") (class "Default")
      (node (ref "C34") (pin "1") (pinfunction "1_1") (pintype "passive"))
      (node (ref "IC8") (pin "3") (pinfunction "IN+_3") (pintype "input"))
      (node (ref "R9") (pin "2") (pinfunction "2_2") (pintype "passive"))
    )
    (net (code "55") (name "Net-(IC8-OUT)") (class "Default")
      (node (ref "IC8") (pin "6") (pinfunction "OUT_6") (pintype "output"))
      (node (ref "R12") (pin "1") (pinfunction "1_1") (pintype "passive"))
    )
    (net (code "56") (name "Net-(IC10-+IN)") (class "Default")
      (node (ref "IC10") (pin "3") (pinfunction "+IN_3") (pintype "input"))
      (node (ref "R13") (pin "1") (pinfunction "1_1") (pintype "passive"))
      (node (ref "R14") (pin "2") (pinfunction "2_2") (pintype "passive"))
    )
    (net (code "57") (name "Net-(IC10--IN)") (class "Default")
      (node (ref "IC10") (pin "1") (pinfunction "OUT_1") (pintype "output"))
      (node (ref "IC10") (pin "4") (pinfunction "-IN_4") (pintype "input"))
      (node (ref "R16") (pin "1") (pinfunction "1_1") (pintype "passive"))
    )
    (net (code "58") (name "Net-(IC11-IN+)") (class "Default")
      (node (ref "C38") (pin "1") (pinfunction "1_1") (pintype "passive"))
      (node (ref "IC11") (pin "3") (pinfunction "IN+_3") (pintype "input"))
      (node (ref "R15") (pin "2") (pinfunction "2_2") (pintype "passive"))
    )
    (net (code "59") (name "Net-(IC11-OUT)") (class "Default")
      (node (ref "IC11") (pin "6") (pinfunction "OUT_6") (pintype "output"))
      (node (ref "R19") (pin "1") (pinfunction "1_1") (pintype "passive"))
    )
    (net (code "60") (name "Net-(IC18-+IN)") (class "Default")
      (node (ref "IC18") (pin "3") (pinfunction "+IN_3") (pintype "input"))
      (node (ref "R50") (pin "1") (pinfunction "1_1") (pintype "passive"))
      (node (ref "R51") (pin "2") (pinfunction "2_2") (pintype "passive"))
    )
    (net (code "61") (name "Net-(IC18--IN)") (class "Default")
      (node (ref "IC18") (pin "1") (pinfunction "OUT_1") (pintype "output"))
      (node (ref "IC18") (pin "4") (pinfunction "-IN_4") (pintype "input"))
      (node (ref "R48") (pin "1") (pinfunction "1_1") (pintype "passive"))
    )
    (net (code "62") (name "Net-(Q1-D)") (class "Default")
      (node (ref "Q1") (pin "3") (pinfunction "D_3") (pintype "passive"))
      (node (ref "Q2") (pin "1") (pinfunction "G_1") (pintype "passive"))
      (node (ref "R12") (pin "2") (pinfunction "2_2") (pintype "passive"))
    )
    (net (code "63") (name "Net-(Q1-G)") (class "Default")
      (node (ref "C37") (pin "1") (pinfunction "1_1") (pintype "passive"))
      (node (ref "Q1") (pin "1") (pinfunction "G_1") (pintype "passive"))
      (node (ref "R11") (pin "2") (pinfunction "2_2") (pintype "passive"))
    )
    (net (code "64") (name "Net-(Q3-D)") (class "Default")
      (node (ref "Q3") (pin "3") (pinfunction "D_3") (pintype "passive"))
      (node (ref "Q4") (pin "1") (pinfunction "G_1") (pintype "passive"))
      (node (ref "R19") (pin "2") (pinfunction "2_2") (pintype "passive"))
    )
    (net (code "65") (name "Net-(Q3-G)") (class "Default")
      (node (ref "C43") (pin "1") (pinfunction "1_1") (pintype "passive"))
      (node (ref "Q3") (pin "1") (pinfunction "G_1") (pintype "passive"))
      (node (ref "R20") (pin "2") (pinfunction "2_2") (pintype "passive"))
    )
    (net (code "66") (name "Net-(Q5-PadB)") (class "Default")
      (node (ref "Q5") (pin "B") (pinfunction "B_B") (pintype "passive"))
      (node (ref "R21") (pin "2") (pinfunction "2_2") (pintype "passive"))
    )
    (net (code "67") (name "Net-(Q6-PadB)") (class "Default")
      (node (ref "Q6") (pin "B") (pinfunction "B_B") (pintype "passive"))
      (node (ref "R22") (pin "2") (pinfunction "2_2") (pintype "passive"))
    )
    (net (code "68") (name "Net-(Q7-G)") (class "Default")
      (node (ref "Q5") (pin "C") (pinfunction "C_C") (pintype "passive"))
      (node (ref "Q7") (pin "1") (pinfunction "G_1") (pintype "passive"))
      (node (ref "R23") (pin "2") (pinfunction "2_2") (pintype "passive"))
    )
    (net (code "69") (name "Net-(Q8-G)") (class "Default")
      (node (ref "Q6") (pin "C") (pinfunction "C_C") (pintype "passive"))
      (node (ref "Q8") (pin "1") (pinfunction "G_1") (pintype "passive"))
      (node (ref "R24") (pin "2") (pinfunction "2_2") (pintype "passive"))
    )
    (net (code "70") (name "Net-(Q9-PadB)") (class "Default")
      (node (ref "Q9") (pin "B") (pinfunction "B_B") (pintype "passive"))
      (node (ref "R27") (pin "2") (pinfunction "2_2") (pintype "passive"))
    )
    (net (code "71") (name "Net-(Q10-PadB)") (class "Default")
      (node (ref "Q10") (pin "B") (pinfunction "B_B") (pintype "passive"))
      (node (ref "R28") (pin "2") (pinfunction "2_2") (pintype "passive"))
    )
    (net (code "72") (name "Net-(Q11-G)") (class "Default")
      (node (ref "Q11") (pin "1") (pinfunction "G_1") (pintype "passive"))
      (node (ref "Q9") (pin "C") (pinfunction "C_C") (pintype "passive"))
      (node (ref "R29") (pin "2") (pinfunction "2_2") (pintype "passive"))
    )
    (net (code "73") (name "Net-(Q12-G)") (class "Default")
      (node (ref "Q10") (pin "C") (pinfunction "C_C") (pintype "passive"))
      (node (ref "Q12") (pin "1") (pinfunction "G_1") (pintype "passive"))
      (node (ref "R30") (pin "2") (pinfunction "2_2") (pintype "passive"))
    )
    (net (code "74") (name "Net-(Q16-G)") (class "Default")
      (node (ref "Q16") (pin "1") (pinfunction "G_1") (pintype "passive"))
      (node (ref "R45") (pin "2") (pinfunction "2_2") (pintype "passive"))
    )
    (net (code "75") (name "Net-(Q17-G)") (class "Default")
      (node (ref "Q17") (pin "1") (pinfunction "G_1") (pintype "passive"))
      (node (ref "R46") (pin "2") (pinfunction "2_2") (pintype "passive"))
    )
    (net (code "76") (name "Net-(Q18-G)") (class "Default")
      (node (ref "Q18") (pin "1") (pinfunction "G_1") (pintype "passive"))
      (node (ref "R47") (pin "2") (pinfunction "2_2") (pintype "passive"))
    )
    (net (code "77") (name "Net-(R3-Pad1)") (class "Default")
      (node (ref "R3") (pin "1") (pinfunction "1_1") (pintype "passive"))
      (node (ref "TX") (pin "A") (pinfunction "A_A") (pintype "bidirectional"))
    )
    (net (code "78") (name "Net-(R4-Pad1)") (class "Default")
      (node (ref "R4") (pin "1") (pinfunction "1_1") (pintype "passive"))
      (node (ref "RX") (pin "A") (pinfunction "A_A") (pintype "bidirectional"))
    )
    (net (code "79") (name "Net-(R8-Pad1)") (class "Default")
      (node (ref "R8") (pin "1") (pinfunction "1_1") (pintype "passive"))
      (node (ref "STATE") (pin "A") (pinfunction "A_A") (pintype "bidirectional"))
    )
    (net (code "80") (name "Net-(RI1-Pad1)") (class "Default")
      (node (ref "RI1") (pin "1") (pinfunction "1_1") (pintype "passive"))
      (node (ref "RI2") (pin "2") (pinfunction "2_2") (pintype "passive"))
    )
    (net (code "81") (name "Net-(RI3-Pad1)") (class "Default")
      (node (ref "RI3") (pin "1") (pinfunction "1_1") (pintype "passive"))
      (node (ref "RI4") (pin "2") (pinfunction "2_2") (pintype "passive"))
    )
    (net (code "82") (name "Net-(USB-2)") (class "Default")
      (node (ref "IC1") (pin "P$1") (pinfunction "IO1_P$1") (pintype "bidirectional"))
      (node (ref "USB") (pin "P$2") (pinfunction "2_P$2") (pintype "bidirectional"))
    )
    (net (code "83") (name "Net-(USB-3)") (class "Default")
      (node (ref "IC1") (pin "P$3") (pinfunction "IO2_P$3") (pintype "bidirectional"))
      (node (ref "USB") (pin "P$3") (pinfunction "3_P$3") (pintype "bidirectional"))
    )
    (net (code "84") (name "Net-(USB-P$1)") (class "Default")
      (node (ref "RUSB") (pin "1") (pinfunction "1_1") (pintype "passive"))
      (node (ref "USB") (pin "SHIELD_1") (pinfunction "P$1_SHIELD_1") (pintype "bidirectional"))
    )
    (net (code "85") (name "Net-(USB-P$4)") (class "Default")
      (node (ref "CUSB") (pin "1") (pinfunction "1_1") (pintype "passive"))
      (node (ref "USB") (pin "SHIELD_4") (pinfunction "P$4_SHIELD_4") (pintype "bidirectional"))
    )
    (net (code "86") (name "P5.45V") (class "Default")
      (node (ref "C14") (pin "1") (pinfunction "1_1") (pintype "passive"))
      (node (ref "C8") (pin "1") (pinfunction "1_1") (pintype "passive"))
      (node (ref "C9") (pin "1") (pinfunction "1_1") (pintype "passive"))
      (node (ref "IC2") (pin "P4") (pinfunction "VOUT_P4") (pintype "passive"))
      (node (ref "IC5") (pin "P1") (pinfunction "IN_P1") (pintype "bidirectional"))
      (node (ref "IC5") (pin "P2") (pinfunction "IN_P2") (pintype "bidirectional"))
      (node (ref "IC5") (pin "P8") (pinfunction "EN_P8") (pintype "bidirectional"))
      (node (ref "RTUNE") (pin "2") (pinfunction "2_2") (pintype "passive"))
    )
    (net (code "87") (name "PDI-CLK") (class "Default")
      (node (ref "IC7") (pin "90") (pinfunction "PDI-CLK/~{RESET}_90") (pintype "input"))
      (node (ref "PDI") (pin "5") (pinfunction "5_5") (pintype "passive"))
    )
    (net (code "88") (name "PDI-DATA") (class "Default")
      (node (ref "IC7") (pin "89") (pinfunction "PDI-DATA_89") (pintype "bidirectional"))
      (node (ref "PDI") (pin "1") (pinfunction "1_1") (pintype "passive"))
    )
    (net (code "89") (name "PK0_IN") (class "Default")
      (node (ref "IC12") (pin "4") (pinfunction "P$4_4") (pintype "bidirectional"))
      (node (ref "IC7") (pin "29") (pinfunction "PD4(OC1A/~{SS})_29") (pintype "bidirectional"))
    )
    (net (code "90") (name "PK0_IO") (class "Default")
      (node (ref "IC7") (pin "30") (pinfunction "PD5(OC1B/XCK1/MOSI)_30") (pintype "bidirectional"))
      (node (ref "Q15") (pin "2") (pinfunction "S_2") (pintype "passive"))
      (node (ref "R35") (pin "2") (pinfunction "2_2") (pintype "passive"))
    )
    (net (code "91") (name "PK0_OUT") (class "Default")
      (node (ref "IC13") (pin "2") (pinfunction "P$2_2") (pintype "bidirectional"))
      (node (ref "IC7") (pin "31") (pinfunction "PD6(RXD1/MISO)_31") (pintype "bidirectional"))
      (node (ref "R40") (pin "2") (pinfunction "2_2") (pintype "passive"))
    )
    (net (code "92") (name "PK0_VAL") (class "Default")
      (node (ref "IC7") (pin "32") (pinfunction "PD7(TXD1/SCK/CLKO/EVO)_32") (pintype "bidirectional"))
      (node (ref "R45") (pin "1") (pinfunction "1_1") (pintype "passive"))
    )
    (net (code "93") (name "PK1_IN") (class "Default")
      (node (ref "IC14") (pin "4") (pinfunction "P$4_4") (pintype "bidirectional"))
      (node (ref "IC7") (pin "39") (pinfunction "PE4(OC1A/~{SS})_39") (pintype "bidirectional"))
    )
    (net (code "94") (name "PK1_IO") (class "Default")
      (node (ref "IC7") (pin "40") (pinfunction "PE5(OC1B/XCK1/MOSI)_40") (pintype "bidirectional"))
      (node (ref "Q13") (pin "2") (pinfunction "S_2") (pintype "passive"))
      (node (ref "R33") (pin "2") (pinfunction "2_2") (pintype "passive"))
    )
    (net (code "95") (name "PK1_OUT") (class "Default")
      (node (ref "IC15") (pin "2") (pinfunction "P$2_2") (pintype "bidirectional"))
      (node (ref "IC7") (pin "41") (pinfunction "PE6(RSC1/MISO/TOSC2)_41") (pintype "bidirectional"))
      (node (ref "R42") (pin "2") (pinfunction "2_2") (pintype "passive"))
    )
    (net (code "96") (name "PK1_VAL") (class "Default")
      (node (ref "IC7") (pin "42") (pinfunction "PE7(TSD1/SCK/CLKO/EVO/TOSC1)_42") (pintype "bidirectional"))
      (node (ref "R46") (pin "1") (pinfunction "1_1") (pintype "passive"))
    )
    (net (code "97") (name "PK2_IN") (class "Default")
      (node (ref "IC16") (pin "4") (pinfunction "P$4_4") (pintype "bidirectional"))
      (node (ref "IC7") (pin "49") (pinfunction "PF4(OC1A/~{SS})_49") (pintype "bidirectional"))
    )
    (net (code "98") (name "PK2_IO") (class "Default")
      (node (ref "IC7") (pin "50") (pinfunction "PF5(OC1B/XCK1/MOSI)_50") (pintype "bidirectional"))
      (node (ref "Q14") (pin "2") (pinfunction "S_2") (pintype "passive"))
      (node (ref "R34") (pin "2") (pinfunction "2_2") (pintype "passive"))
    )
    (net (code "99") (name "PK2_OUT") (class "Default")
      (node (ref "IC17") (pin "2") (pinfunction "P$2_2") (pintype "bidirectional"))
      (node (ref "IC7") (pin "51") (pinfunction "PF6(RXD1/MISO)_51") (pintype "bidirectional"))
      (node (ref "R44") (pin "1") (pinfunction "1_1") (pintype "passive"))
    )
    (net (code "100") (name "PK2_VAL") (class "Default")
      (node (ref "IC7") (pin "52") (pinfunction "PF7(TXD1/SCK)_52") (pintype "bidirectional"))
      (node (ref "R47") (pin "1") (pinfunction "1_1") (pintype "passive"))
    )
    (net (code "101") (name "SERIAL_LED0") (class "Default")
      (node (ref "J1") (pin "2") (pinfunction "S_2") (pintype "passive"))
      (node (ref "R7") (pin "1") (pinfunction "1_1") (pintype "passive"))
    )
    (net (code "102") (name "STATE") (class "Default")
      (node (ref "IC7") (pin "1") (pinfunction "PA6(ADCA6)_1") (pintype "bidirectional"))
      (node (ref "R8") (pin "2") (pinfunction "2_2") (pintype "passive"))
    )
    (net (code "103") (name "TOG_D00") (class "Default")
      (node (ref "IC7") (pin "45") (pinfunction "PF0(OC0A/SDA)_45") (pintype "bidirectional"))
      (node (ref "R28") (pin "1") (pinfunction "1_1") (pintype "passive"))
    )
    (net (code "104") (name "TOG_D01") (class "Default")
      (node (ref "IC7") (pin "35") (pinfunction "PE0(OC0A/SDA)_35") (pintype "bidirectional"))
      (node (ref "R22") (pin "1") (pinfunction "1_1") (pintype "passive"))
    )
    (net (code "105") (name "TOG_D02") (class "Default")
      (node (ref "IC7") (pin "25") (pinfunction "PD0(OC0A/SDA)_25") (pintype "bidirectional"))
      (node (ref "R27") (pin "1") (pinfunction "1_1") (pintype "passive"))
    )
    (net (code "106") (name "TOG_D03") (class "Default")
      (node (ref "IC7") (pin "15") (pinfunction "PC0(OC0A/SDA)_15") (pintype "bidirectional"))
      (node (ref "R21") (pin "1") (pinfunction "1_1") (pintype "passive"))
    )
    (net (code "107") (name "USBDM") (class "Default")
      (node (ref "C7") (pin "1") (pinfunction "1_1") (pintype "passive"))
      (node (ref "IC1") (pin "P$6") (pinfunction "IO1_P$6") (pintype "bidirectional"))
      (node (ref "IC4") (pin "16") (pinfunction "USBDM_16") (pintype "bidirectional"))
    )
    (net (code "108") (name "USBDP") (class "Default")
      (node (ref "C6") (pin "1") (pinfunction "1_1") (pintype "passive"))
      (node (ref "IC1") (pin "P$4") (pinfunction "IO2_P$4") (pintype "bidirectional"))
      (node (ref "IC4") (pin "15") (pinfunction "USBDP_15") (pintype "bidirectional"))
    )
    (net (code "109") (name "VAL_PK0") (class "Default")
      (node (ref "D1") (pin "A") (pinfunction "A_A") (pintype "passive"))
      (node (ref "J2") (pin "7") (pinfunction "7_7") (pintype "passive"))
      (node (ref "Q16") (pin "2") (pinfunction "D_2") (pintype "passive"))
      (node (ref "Q16") (pin "4") (pinfunction "D_4") (pintype "passive"))
    )
    (net (code "110") (name "VAL_PK1") (class "Default")
      (node (ref "D2") (pin "A") (pinfunction "A_A") (pintype "passive"))
      (node (ref "J3") (pin "7") (pinfunction "7_7") (pintype "passive"))
      (node (ref "Q17") (pin "2") (pinfunction "D_2") (pintype "passive"))
      (node (ref "Q17") (pin "4") (pinfunction "D_4") (pintype "passive"))
    )
    (net (code "111") (name "VAL_PK2") (class "Default")
      (node (ref "D3") (pin "A") (pinfunction "A_A") (pintype "passive"))
      (node (ref "J4") (pin "7") (pinfunction "7_7") (pintype "passive"))
      (node (ref "Q18") (pin "2") (pinfunction "D_2") (pintype "passive"))
      (node (ref "Q18") (pin "4") (pinfunction "D_4") (pintype "passive"))
    )
    (net (code "112") (name "VCCIO") (class "Default")
      (node (ref "C15") (pin "1") (pinfunction "1_1") (pintype "passive"))
      (node (ref "C16") (pin "1") (pinfunction "1_1") (pintype "passive"))
      (node (ref "C20") (pin "1") (pinfunction "1_1") (pintype "passive"))
      (node (ref "C21") (pin "1") (pinfunction "1_1") (pintype "passive"))
      (node (ref "C22") (pin "1") (pinfunction "1_1") (pintype "passive"))
      (node (ref "C23") (pin "1") (pinfunction "1_1") (pintype "passive"))
      (node (ref "C24") (pin "1") (pinfunction "1_1") (pintype "passive"))
      (node (ref "C26") (pin "1") (pinfunction "1_1") (pintype "passive"))
      (node (ref "C28") (pin "1") (pinfunction "1_1") (pintype "passive"))
      (node (ref "C30") (pin "1") (pinfunction "1_1") (pintype "passive"))
      (node (ref "C31") (pin "1") (pinfunction "1_1") (pintype "passive"))
      (node (ref "C32") (pin "1") (pinfunction "1_1") (pintype "passive"))
      (node (ref "C44") (pin "1") (pinfunction "1_1") (pintype "passive"))
      (node (ref "C46") (pin "1") (pinfunction "1_1") (pintype "passive"))
      (node (ref "C48") (pin "1") (pinfunction "1_1") (pintype "passive"))
      (node (ref "C53") (pin "1") (pinfunction "1_1") (pintype "passive"))
      (node (ref "CLKIN") (pin "1") (pinfunction "1_1") (pintype "passive"))
      (node (ref "D4") (pin "A") (pinfunction "A_A") (pintype "passive"))
      (node (ref "IC12") (pin "5") (pinfunction "P$5_5") (pintype "bidirectional"))
      (node (ref "IC14") (pin "5") (pinfunction "P$5_5") (pintype "bidirectional"))
      (node (ref "IC16") (pin "5") (pinfunction "P$5_5") (pintype "bidirectional"))
      (node (ref "IC19") (pin "5") (pinfunction "P$5_5") (pintype "bidirectional"))
      (node (ref "IC3") (pin "5") (pinfunction "OUT_5") (pintype "bidirectional"))
      (node (ref "IC4") (pin "4") (pinfunction "VCCIO_4") (pintype "power_in"))
      (node (ref "IC7") (pin "14") (pinfunction "VCC_14") (pintype "power_in"))
      (node (ref "IC7") (pin "24") (pinfunction "VCC_24") (pintype "power_in"))
      (node (ref "IC7") (pin "34") (pinfunction "VCC_34") (pintype "power_in"))
      (node (ref "IC7") (pin "44") (pinfunction "VCC_44") (pintype "power_in"))
      (node (ref "IC7") (pin "54") (pinfunction "VCC_54") (pintype "power_in"))
      (node (ref "IC7") (pin "64") (pinfunction "VCC_64") (pintype "power_in"))
      (node (ref "IC7") (pin "65") (pinfunction "PJ0(D0/A0/A8)_65") (pintype "bidirectional"))
      (node (ref "IC7") (pin "74") (pinfunction "VCC_74") (pintype "power_in"))
      (node (ref "IC7") (pin "83") (pinfunction "VCC_83") (pintype "power_in"))
      (node (ref "OSC1") (pin "P$4") (pinfunction "VDD_P$4") (pintype "passive"))
      (node (ref "PDI") (pin "2") (pinfunction "2_2") (pintype "passive"))
      (node (ref "Q13") (pin "1") (pinfunction "G_1") (pintype "passive"))
      (node (ref "Q14") (pin "1") (pinfunction "G_1") (pintype "passive"))
      (node (ref "Q15") (pin "1") (pinfunction "G_1") (pintype "passive"))
      (node (ref "R10") (pin "1") (pinfunction "1_1") (pintype "passive"))
      (node (ref "R17") (pin "1") (pinfunction "1_1") (pintype "passive"))
      (node (ref "R33") (pin "1") (pinfunction "1_1") (pintype "passive"))
      (node (ref "R34") (pin "1") (pinfunction "1_1") (pintype "passive"))
      (node (ref "R35") (pin "1") (pinfunction "1_1") (pintype "passive"))
    )
    (net (code "113") (name "VDD") (class "Default")
      (node (ref "C25") (pin "1") (pinfunction "1_1") (pintype "passive"))
      (node (ref "C27") (pin "1") (pinfunction "1_1") (pintype "passive"))
      (node (ref "C29") (pin "1") (pinfunction "1_1") (pintype "passive"))
      (node (ref "C36") (pin "1") (pinfunction "1_1") (pintype "passive"))
      (node (ref "C39") (pin "1") (pinfunction "1_1") (pintype "passive"))
      (node (ref "C52") (pin "1") (pinfunction "1_1") (pintype "passive"))
      (node (ref "D4") (pin "C") (pinfunction "C_C") (pintype "passive"))
      (node (ref "IC10") (pin "5") (pinfunction "V+_5") (pintype "power_in"))
      (node (ref "IC18") (pin "5") (pinfunction "V+_5") (pintype "power_in"))
      (node (ref "IC7") (pin "4") (pinfunction "AVCC-B_4") (pintype "power_in"))
      (node (ref "IC7") (pin "94") (pinfunction "AVCC-A_94") (pintype "power_in"))
      (node (ref "IC9") (pin "5") (pinfunction "OUT_5") (pintype "bidirectional"))
    )
    (net (code "114") (name "unconnected-(IC3-N{slash}C-Pad4)") (class "Default")
      (node (ref "IC3") (pin "4") (pinfunction "N/C_4") (pintype "bidirectional"))
    )
    (net (code "115") (name "unconnected-(IC4-CBUS2-Pad13)") (class "Default")
      (node (ref "IC4") (pin "13") (pinfunction "CBUS2_13") (pintype "bidirectional"))
    )
    (net (code "116") (name "unconnected-(IC4-CBUS3-Pad14)") (class "Default")
      (node (ref "IC4") (pin "14") (pinfunction "CBUS3_14") (pintype "bidirectional"))
    )
    (net (code "117") (name "unconnected-(IC4-CBUS4-Pad12)") (class "Default")
      (node (ref "IC4") (pin "12") (pinfunction "CBUS4_12") (pintype "bidirectional"))
    )
    (net (code "118") (name "unconnected-(IC4-OSCI-Pad27)") (class "Default")
      (node (ref "IC4") (pin "27") (pinfunction "OSCI_27") (pintype "input"))
    )
    (net (code "119") (name "unconnected-(IC4-OSCO-Pad28)") (class "Default")
      (node (ref "IC4") (pin "28") (pinfunction "OSCO_28") (pintype "output"))
    )
    (net (code "120") (name "unconnected-(IC4-~{DCD}-Pad10)") (class "Default")
      (node (ref "IC4") (pin "10") (pinfunction "~{DCD}_10") (pintype "input"))
    )
    (net (code "121") (name "unconnected-(IC4-~{DSR}-Pad9)") (class "Default")
      (node (ref "IC4") (pin "9") (pinfunction "~{DSR}_9") (pintype "input"))
    )
    (net (code "122") (name "unconnected-(IC4-~{DTR}-Pad2)") (class "Default")
      (node (ref "IC4") (pin "2") (pinfunction "~{DTR}_2") (pintype "output"))
    )
    (net (code "123") (name "unconnected-(IC4-~{RESET}-Pad19)") (class "Default")
      (node (ref "IC4") (pin "19") (pinfunction "~{RESET}_19") (pintype "input"))
    )
    (net (code "124") (name "unconnected-(IC4-~{RI}-Pad6)") (class "Default")
      (node (ref "IC4") (pin "6") (pinfunction "~{RI}_6") (pintype "input"))
    )
    (net (code "125") (name "unconnected-(IC7-PA3(ADCA3)-Pad98)") (class "Default")
      (node (ref "IC7") (pin "98") (pinfunction "PA3(ADCA3)_98") (pintype "bidirectional"))
    )
    (net (code "126") (name "unconnected-(IC7-PA4(ADCA4)-Pad99)") (class "Default")
      (node (ref "IC7") (pin "99") (pinfunction "PA4(ADCA4)_99") (pintype "bidirectional"))
    )
    (net (code "127") (name "unconnected-(IC7-PA5(ADCA5)-Pad100)") (class "Default")
      (node (ref "IC7") (pin "100") (pinfunction "PA5(ADCA5)_100") (pintype "bidirectional"))
    )
    (net (code "128") (name "unconnected-(IC7-PA7{slash}(ADCA7{slash}AC0-OUT)-Pad2)") (class "Default")
      (node (ref "IC7") (pin "2") (pinfunction "PA7/(ADCA7/AC0-OUT)_2") (pintype "bidirectional"))
    )
    (net (code "129") (name "unconnected-(IC7-PB0(ADCB0{slash}AREFB)-Pad5)") (class "Default")
      (node (ref "IC7") (pin "5") (pinfunction "PB0(ADCB0/AREFB)_5") (pintype "bidirectional"))
    )
    (net (code "130") (name "unconnected-(IC7-PB1(ADCB1)-Pad6)") (class "Default")
      (node (ref "IC7") (pin "6") (pinfunction "PB1(ADCB1)_6") (pintype "bidirectional"))
    )
    (net (code "131") (name "unconnected-(IC7-PB4(ADCB4{slash}TMS)-Pad9)") (class "Default")
      (node (ref "IC7") (pin "9") (pinfunction "PB4(ADCB4/TMS)_9") (pintype "bidirectional"))
    )
    (net (code "132") (name "unconnected-(IC7-PB7(ADCB7{slash}AC0-OUT{slash}TDO)-Pad12)") (class "Default")
      (node (ref "IC7") (pin "12") (pinfunction "PB7(ADCB7/AC0-OUT/TDO)_12") (pintype "bidirectional"))
    )
    (net (code "133") (name "unconnected-(IC7-PC1(OC0B{slash}XCK0{slash}SCL)-Pad16)") (class "Default")
      (node (ref "IC7") (pin "16") (pinfunction "PC1(OC0B/XCK0/SCL)_16") (pintype "bidirectional"))
    )
    (net (code "134") (name "unconnected-(IC7-PC2(OC0C{slash}RXD0)-Pad17)") (class "Default")
      (node (ref "IC7") (pin "17") (pinfunction "PC2(OC0C/RXD0)_17") (pintype "bidirectional"))
    )
    (net (code "135") (name "unconnected-(IC7-PC3(OC0D{slash}TXD0)-Pad18)") (class "Default")
      (node (ref "IC7") (pin "18") (pinfunction "PC3(OC0D/TXD0)_18") (pintype "bidirectional"))
    )
    (net (code "136") (name "unconnected-(IC7-PC4(OC1A{slash}~{SS})-Pad19)") (class "Default")
      (node (ref "IC7") (pin "19") (pinfunction "PC4(OC1A/~{SS})_19") (pintype "bidirectional"))
    )
    (net (code "137") (name "unconnected-(IC7-PC7(SCK{slash}TXD1{slash}CLKO{slash}EVO)-Pad22)") (class "Default")
      (node (ref "IC7") (pin "22") (pinfunction "PC7(SCK/TXD1/CLKO/EVO)_22") (pintype "bidirectional"))
    )
    (net (code "138") (name "unconnected-(IC7-PD1(OC0B{slash}XCK0{slash}SCL)-Pad26)") (class "Default")
      (node (ref "IC7") (pin "26") (pinfunction "PD1(OC0B/XCK0/SCL)_26") (pintype "bidirectional"))
    )
    (net (code "139") (name "unconnected-(IC7-PD2(OC0C{slash}RXD0)-Pad27)") (class "Default")
      (node (ref "IC7") (pin "27") (pinfunction "PD2(OC0C/RXD0)_27") (pintype "bidirectional"))
    )
    (net (code "140") (name "unconnected-(IC7-PD3(OC0D{slash}TXD0)-Pad28)") (class "Default")
      (node (ref "IC7") (pin "28") (pinfunction "PD3(OC0D/TXD0)_28") (pintype "bidirectional"))
    )
    (net (code "141") (name "unconnected-(IC7-PE1(OC0B{slash}XCK0{slash}SCL)-Pad36)") (class "Default")
      (node (ref "IC7") (pin "36") (pinfunction "PE1(OC0B/XCK0/SCL)_36") (pintype "bidirectional"))
    )
    (net (code "142") (name "unconnected-(IC7-PE2(OC0C{slash}RXD0)-Pad37)") (class "Default")
      (node (ref "IC7") (pin "37") (pinfunction "PE2(OC0C/RXD0)_37") (pintype "bidirectional"))
    )
    (net (code "143") (name "unconnected-(IC7-PE3(OC0D{slash}TXD0)-Pad38)") (class "Default")
      (node (ref "IC7") (pin "38") (pinfunction "PE3(OC0D/TXD0)_38") (pintype "bidirectional"))
    )
    (net (code "144") (name "unconnected-(IC7-PF1(OC0B{slash}XCK0{slash}SCL)-Pad46)") (class "Default")
      (node (ref "IC7") (pin "46") (pinfunction "PF1(OC0B/XCK0/SCL)_46") (pintype "bidirectional"))
    )
    (net (code "145") (name "unconnected-(IC7-PH1(~{CAS}{slash}~{RE})-Pad56)") (class "Default")
      (node (ref "IC7") (pin "56") (pinfunction "PH1(~{CAS}/~{RE})_56") (pintype "bidirectional"))
    )
    (net (code "146") (name "unconnected-(IC7-PH2(~{RAS}{slash}ALE1)-Pad57)") (class "Default")
      (node (ref "IC7") (pin "57") (pinfunction "PH2(~{RAS}/ALE1)_57") (pintype "bidirectional"))
    )
    (net (code "147") (name "unconnected-(IC7-PH3(~{DOM}{slash}ALE2)-Pad58)") (class "Default")
      (node (ref "IC7") (pin "58") (pinfunction "PH3(~{DOM}/ALE2)_58") (pintype "bidirectional"))
    )
    (net (code "148") (name "unconnected-(IC7-PH4(BA0{slash}~{CS0}{slash}A16)-Pad59)") (class "Default")
      (node (ref "IC7") (pin "59") (pinfunction "PH4(BA0/~{CS0}/A16)_59") (pintype "bidirectional"))
    )
    (net (code "149") (name "unconnected-(IC7-PH5(BA1{slash}~{CS1}{slash}A17)-Pad60)") (class "Default")
      (node (ref "IC7") (pin "60") (pinfunction "PH5(BA1/~{CS1}/A17)_60") (pintype "bidirectional"))
    )
    (net (code "150") (name "unconnected-(IC7-PH6(CKE{slash}~{CS2}{slash}A18)-Pad61)") (class "Default")
      (node (ref "IC7") (pin "61") (pinfunction "PH6(CKE/~{CS2}/A18)_61") (pintype "bidirectional"))
    )
    (net (code "151") (name "unconnected-(IC7-PH7(CLK{slash}~{CS3}{slash}A19)-Pad62)") (class "Default")
      (node (ref "IC7") (pin "62") (pinfunction "PH7(CLK/~{CS3}/A19)_62") (pintype "bidirectional"))
    )
    (net (code "152") (name "unconnected-(IC7-PJ1(D1{slash}A1{slash}A9)-Pad66)") (class "Default")
      (node (ref "IC7") (pin "66") (pinfunction "PJ1(D1/A1/A9)_66") (pintype "bidirectional"))
    )
    (net (code "153") (name "unconnected-(IC7-PJ2(D2{slash}A2{slash}A10)-Pad67)") (class "Default")
      (node (ref "IC7") (pin "67") (pinfunction "PJ2(D2/A2/A10)_67") (pintype "bidirectional"))
    )
    (net (code "154") (name "unconnected-(IC7-PJ3(D3{slash}A3{slash}A11)-Pad68)") (class "Default")
      (node (ref "IC7") (pin "68") (pinfunction "PJ3(D3/A3/A11)_68") (pintype "bidirectional"))
    )
    (net (code "155") (name "unconnected-(IC7-PJ4(A8{slash}D4{slash}A4{slash}A12)-Pad69)") (class "Default")
      (node (ref "IC7") (pin "69") (pinfunction "PJ4(A8/D4/A4/A12)_69") (pintype "bidirectional"))
    )
    (net (code "156") (name "unconnected-(IC7-PJ5(A9{slash}D5{slash}A5{slash}A13)-Pad70)") (class "Default")
      (node (ref "IC7") (pin "70") (pinfunction "PJ5(A9/D5/A5/A13)_70") (pintype "bidirectional"))
    )
    (net (code "157") (name "unconnected-(IC7-PJ7(A11{slash}D7{slash}A7{slash}A15)-Pad72)") (class "Default")
      (node (ref "IC7") (pin "72") (pinfunction "PJ7(A11/D7/A7/A15)_72") (pintype "bidirectional"))
    )
    (net (code "158") (name "unconnected-(IC7-PK1(A1{slash}A9{slash}A17)-Pad76)") (class "Default")
      (node (ref "IC7") (pin "76") (pinfunction "PK1(A1/A9/A17)_76") (pintype "bidirectional"))
    )
    (net (code "159") (name "unconnected-(IC7-PK2(A2{slash}A10{slash}A18)-Pad77)") (class "Default")
      (node (ref "IC7") (pin "77") (pinfunction "PK2(A2/A10/A18)_77") (pintype "bidirectional"))
    )
    (net (code "160") (name "unconnected-(IC7-PK3(A3{slash}A11{slash}A19)-Pad78)") (class "Default")
      (node (ref "IC7") (pin "78") (pinfunction "PK3(A3/A11/A19)_78") (pintype "bidirectional"))
    )
    (net (code "161") (name "unconnected-(IC7-PK4(A4{slash}A12{slash}A20)-Pad79)") (class "Default")
      (node (ref "IC7") (pin "79") (pinfunction "PK4(A4/A12/A20)_79") (pintype "bidirectional"))
    )
    (net (code "162") (name "unconnected-(IC7-PK5(A5{slash}A13{slash}A22)-Pad80)") (class "Default")
      (node (ref "IC7") (pin "80") (pinfunction "PK5(A5/A13/A22)_80") (pintype "bidirectional"))
    )
    (net (code "163") (name "unconnected-(IC7-PK6(A6{slash}A14{slash}A22)-Pad81)") (class "Default")
      (node (ref "IC7") (pin "81") (pinfunction "PK6(A6/A14/A22)_81") (pintype "bidirectional"))
    )
    (net (code "164") (name "unconnected-(IC7-PK7(A7{slash}A15{slash}A23)-Pad82)") (class "Default")
      (node (ref "IC7") (pin "82") (pinfunction "PK7(A7/A15/A23)_82") (pintype "bidirectional"))
    )
    (net (code "165") (name "unconnected-(IC7-PQ0(TOSC1)-Pad85)") (class "Default")
      (node (ref "IC7") (pin "85") (pinfunction "PQ0(TOSC1)_85") (pintype "bidirectional"))
    )
    (net (code "166") (name "unconnected-(IC7-PQ1(TOSC2)-Pad86)") (class "Default")
      (node (ref "IC7") (pin "86") (pinfunction "PQ1(TOSC2)_86") (pintype "bidirectional"))
    )
    (net (code "167") (name "unconnected-(IC7-PQ2-Pad87)") (class "Default")
      (node (ref "IC7") (pin "87") (pinfunction "PQ2_87") (pintype "bidirectional"))
    )
    (net (code "168") (name "unconnected-(IC7-PQ3-Pad88)") (class "Default")
      (node (ref "IC7") (pin "88") (pinfunction "PQ3_88") (pintype "bidirectional"))
    )
    (net (code "169") (name "unconnected-(IC7-PR0(XTAL2)-Pad91)") (class "Default")
      (node (ref "IC7") (pin "91") (pinfunction "PR0(XTAL2)_91") (pintype "bidirectional"))
    )
    (net (code "170") (name "unconnected-(IC8-DISABLE-Pad8)") (class "Default")
      (node (ref "IC8") (pin "8") (pinfunction "DISABLE_8") (pintype "passive"))
    )
    (net (code "171") (name "unconnected-(IC9-N{slash}C-Pad4)") (class "Default")
      (node (ref "IC9") (pin "4") (pinfunction "N/C_4") (pintype "bidirectional"))
    )
    (net (code "172") (name "unconnected-(IC11-DISABLE-Pad8)") (class "Default")
      (node (ref "IC11") (pin "8") (pinfunction "DISABLE_8") (pintype "passive"))
    )
    (net (code "173") (name "unconnected-(J2-Pad8)") (class "Default")
      (node (ref "J2") (pin "8") (pinfunction "8_8") (pintype "passive"))
    )
    (net (code "174") (name "unconnected-(J3-Pad8)") (class "Default")
      (node (ref "J3") (pin "8") (pinfunction "8_8") (pintype "passive"))
    )
    (net (code "175") (name "unconnected-(J4-Pad8)") (class "Default")
      (node (ref "J4") (pin "8") (pinfunction "8_8") (pintype "passive"))
    )
    (net (code "176") (name "unconnected-(OSC1-STANDBY#-PadP$1)") (class "Default")
      (node (ref "OSC1") (pin "P$1") (pinfunction "STANDBY#_P$1") (pintype "passive"))
    )
    (net (code "177") (name "unconnected-(PDI-Pad3)") (class "Default")
      (node (ref "PDI") (pin "3") (pinfunction "3_3") (pintype "passive"))
    )
    (net (code "178") (name "unconnected-(PDI-Pad4)") (class "Default")
      (node (ref "PDI") (pin "4") (pinfunction "4_4") (pintype "passive"))
    )
    (net (code "179") (name "unconnected-(USB-4-PadP$4)") (class "Default")
      (node (ref "USB") (pin "P$4") (pinfunction "4_P$4") (pintype "bidirectional"))
    )
    (net (code "180") (name "unconnected-(USB-P$2-PadSHIELD_2)") (class "Default")
      (node (ref "USB") (pin "SHIELD_2") (pinfunction "P$2_SHIELD_2") (pintype "bidirectional"))
    )
    (net (code "181") (name "unconnected-(USB-P$3-PadSHIELD_3)") (class "Default")
      (node (ref "USB") (pin "SHIELD_3") (pinfunction "P$3_SHIELD_3") (pintype "bidirectional"))
    )
  )
)
